# New_U540.net
KiCad netlist of a schematic drawn in EAGLE
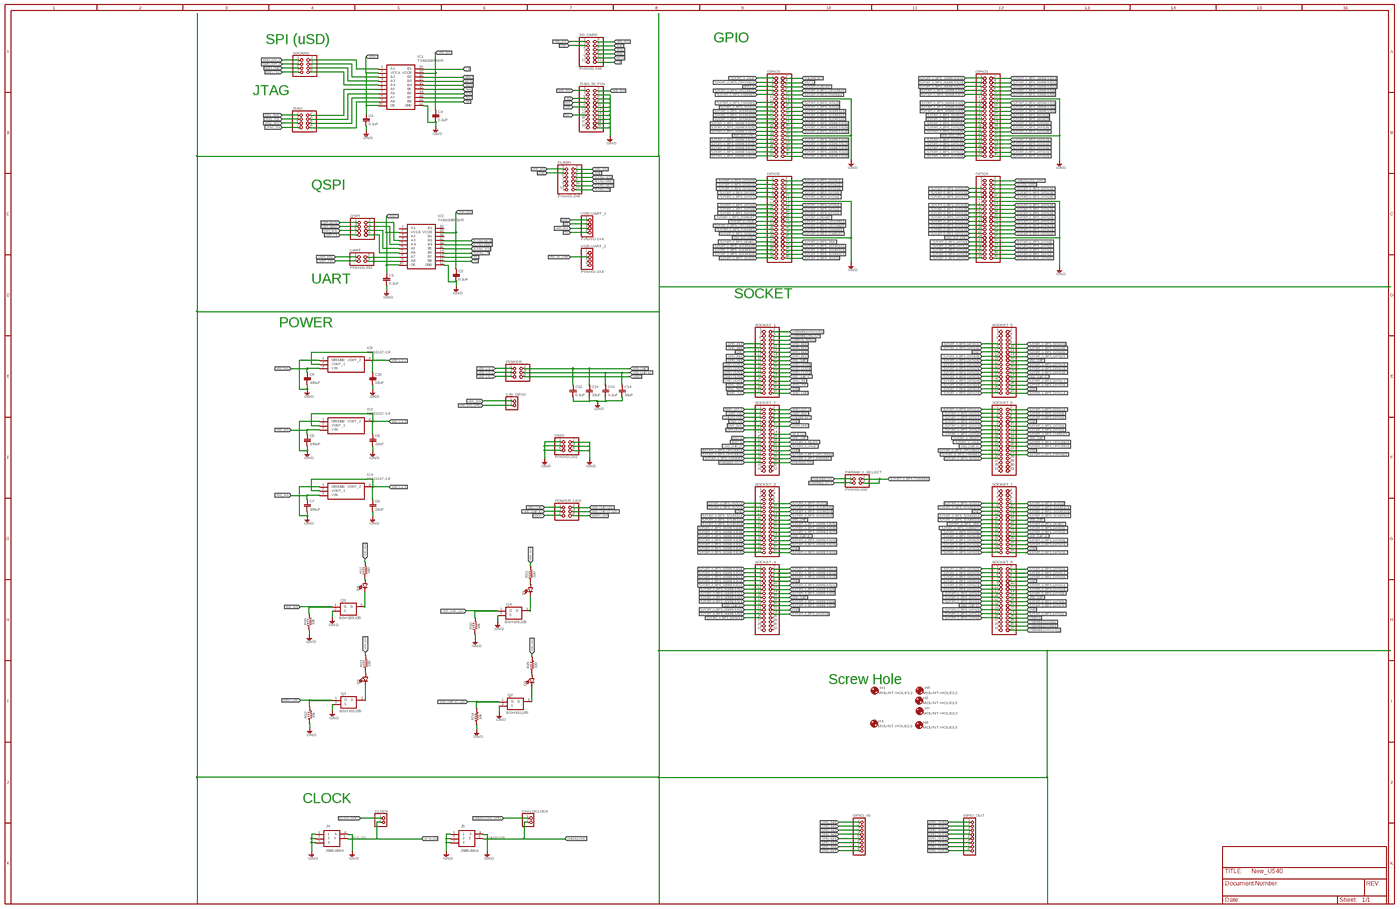
[diagram p0: schematic, sheet 1, overview]
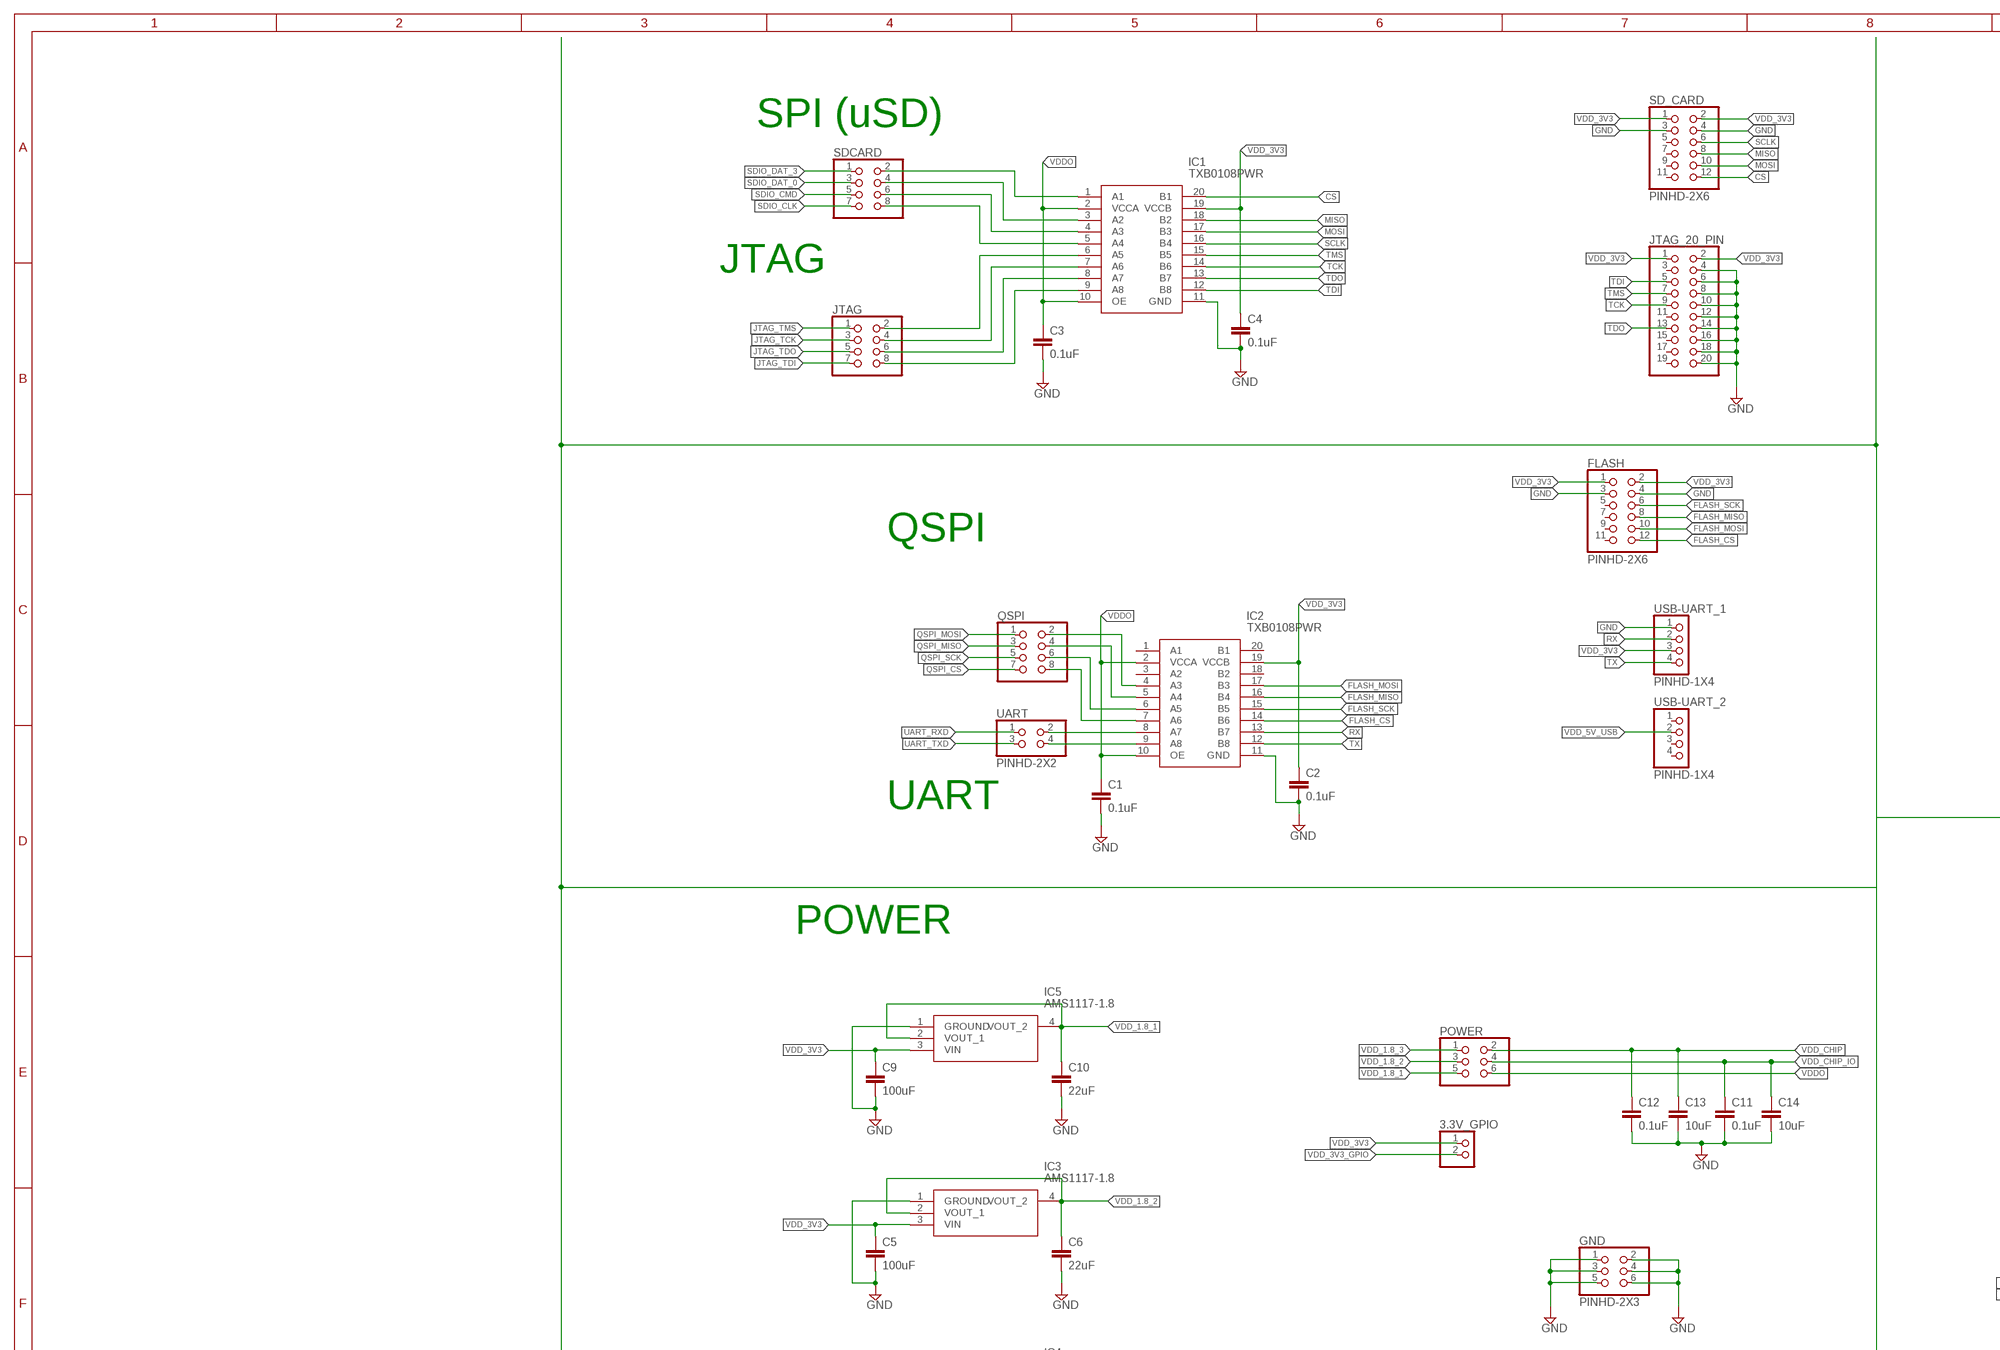
[diagram p1: schematic, sheet 1, part 1 of 4]
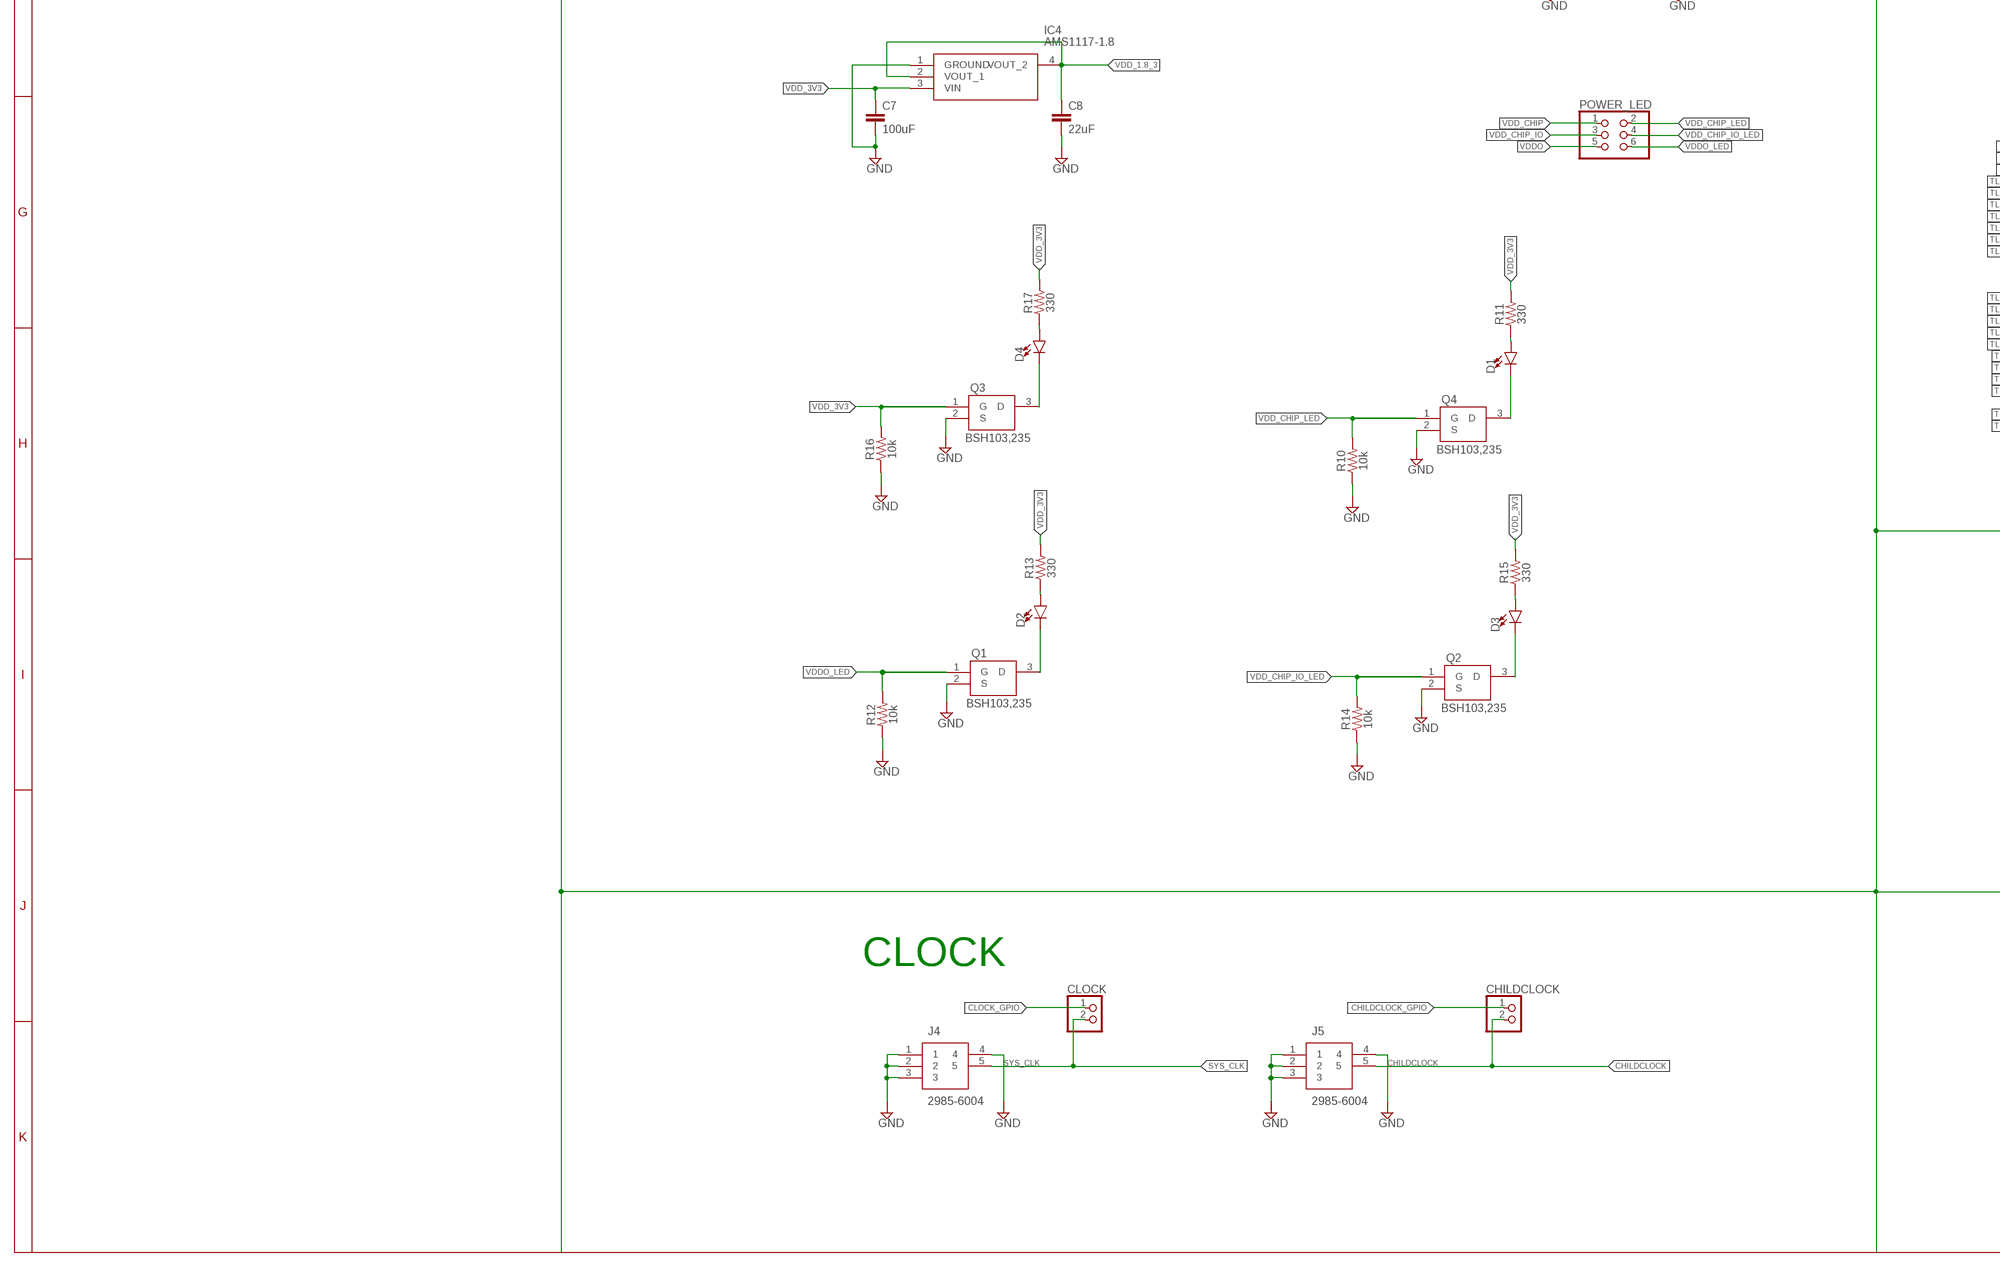
[diagram p2: schematic, sheet 1, part 2 of 4]
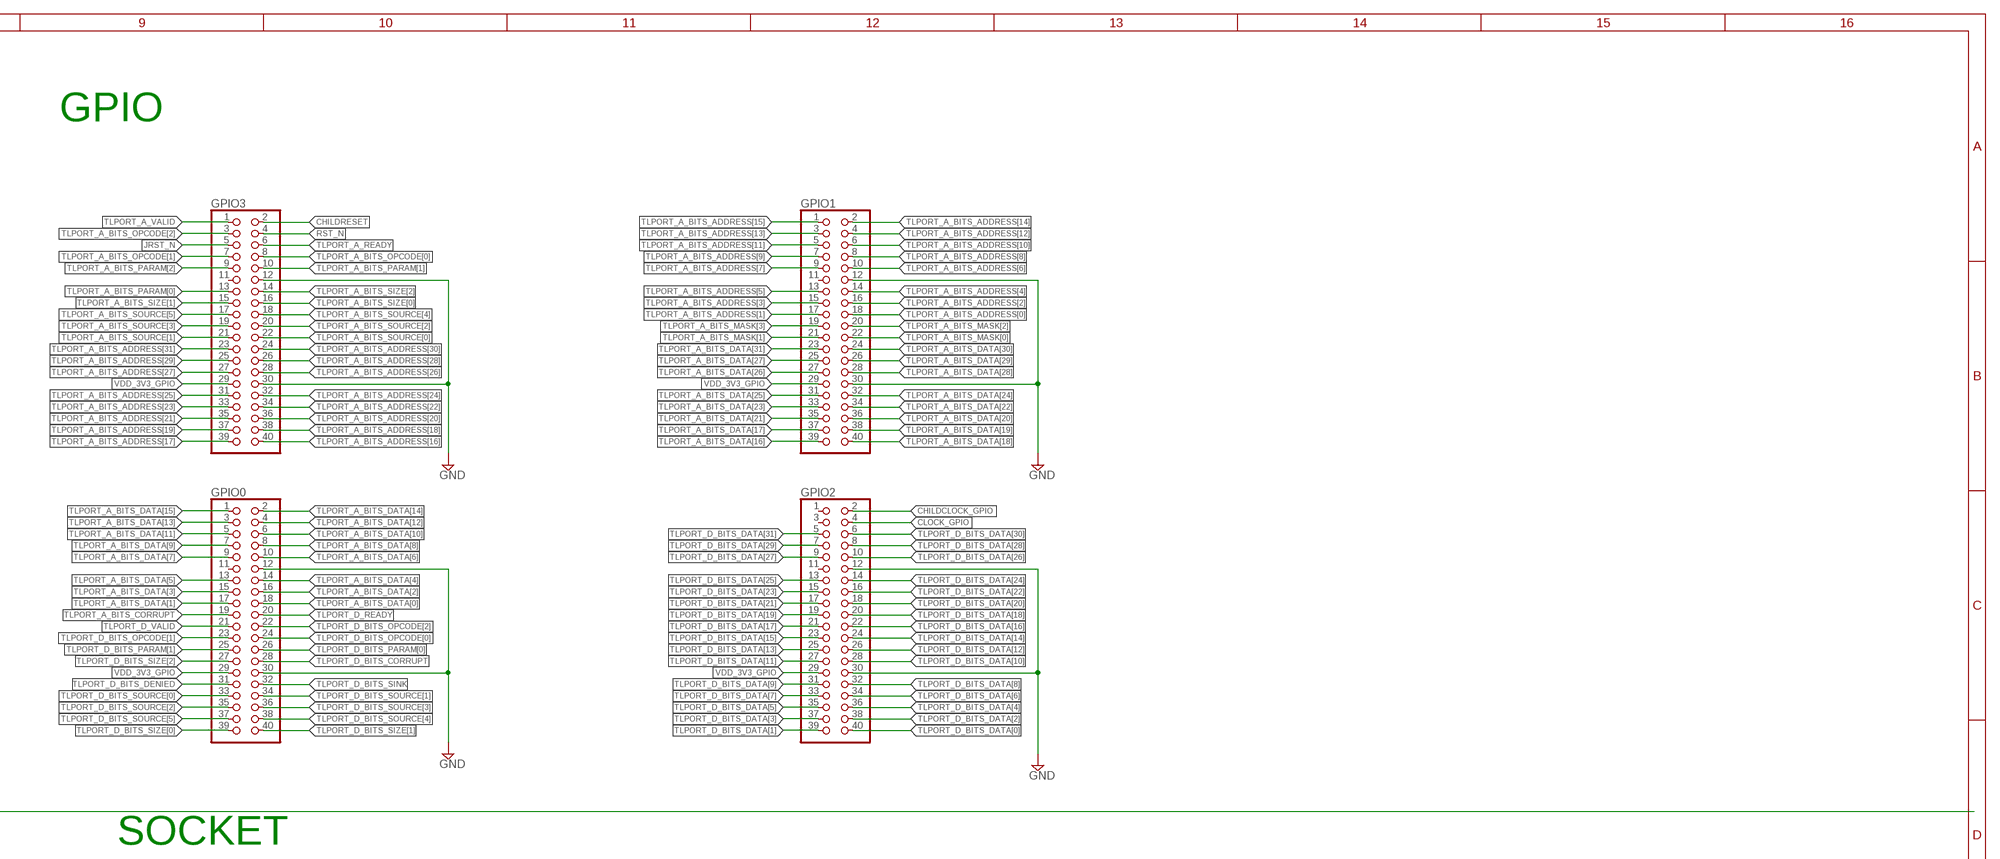
[diagram p3: schematic, sheet 1, part 3 of 4]
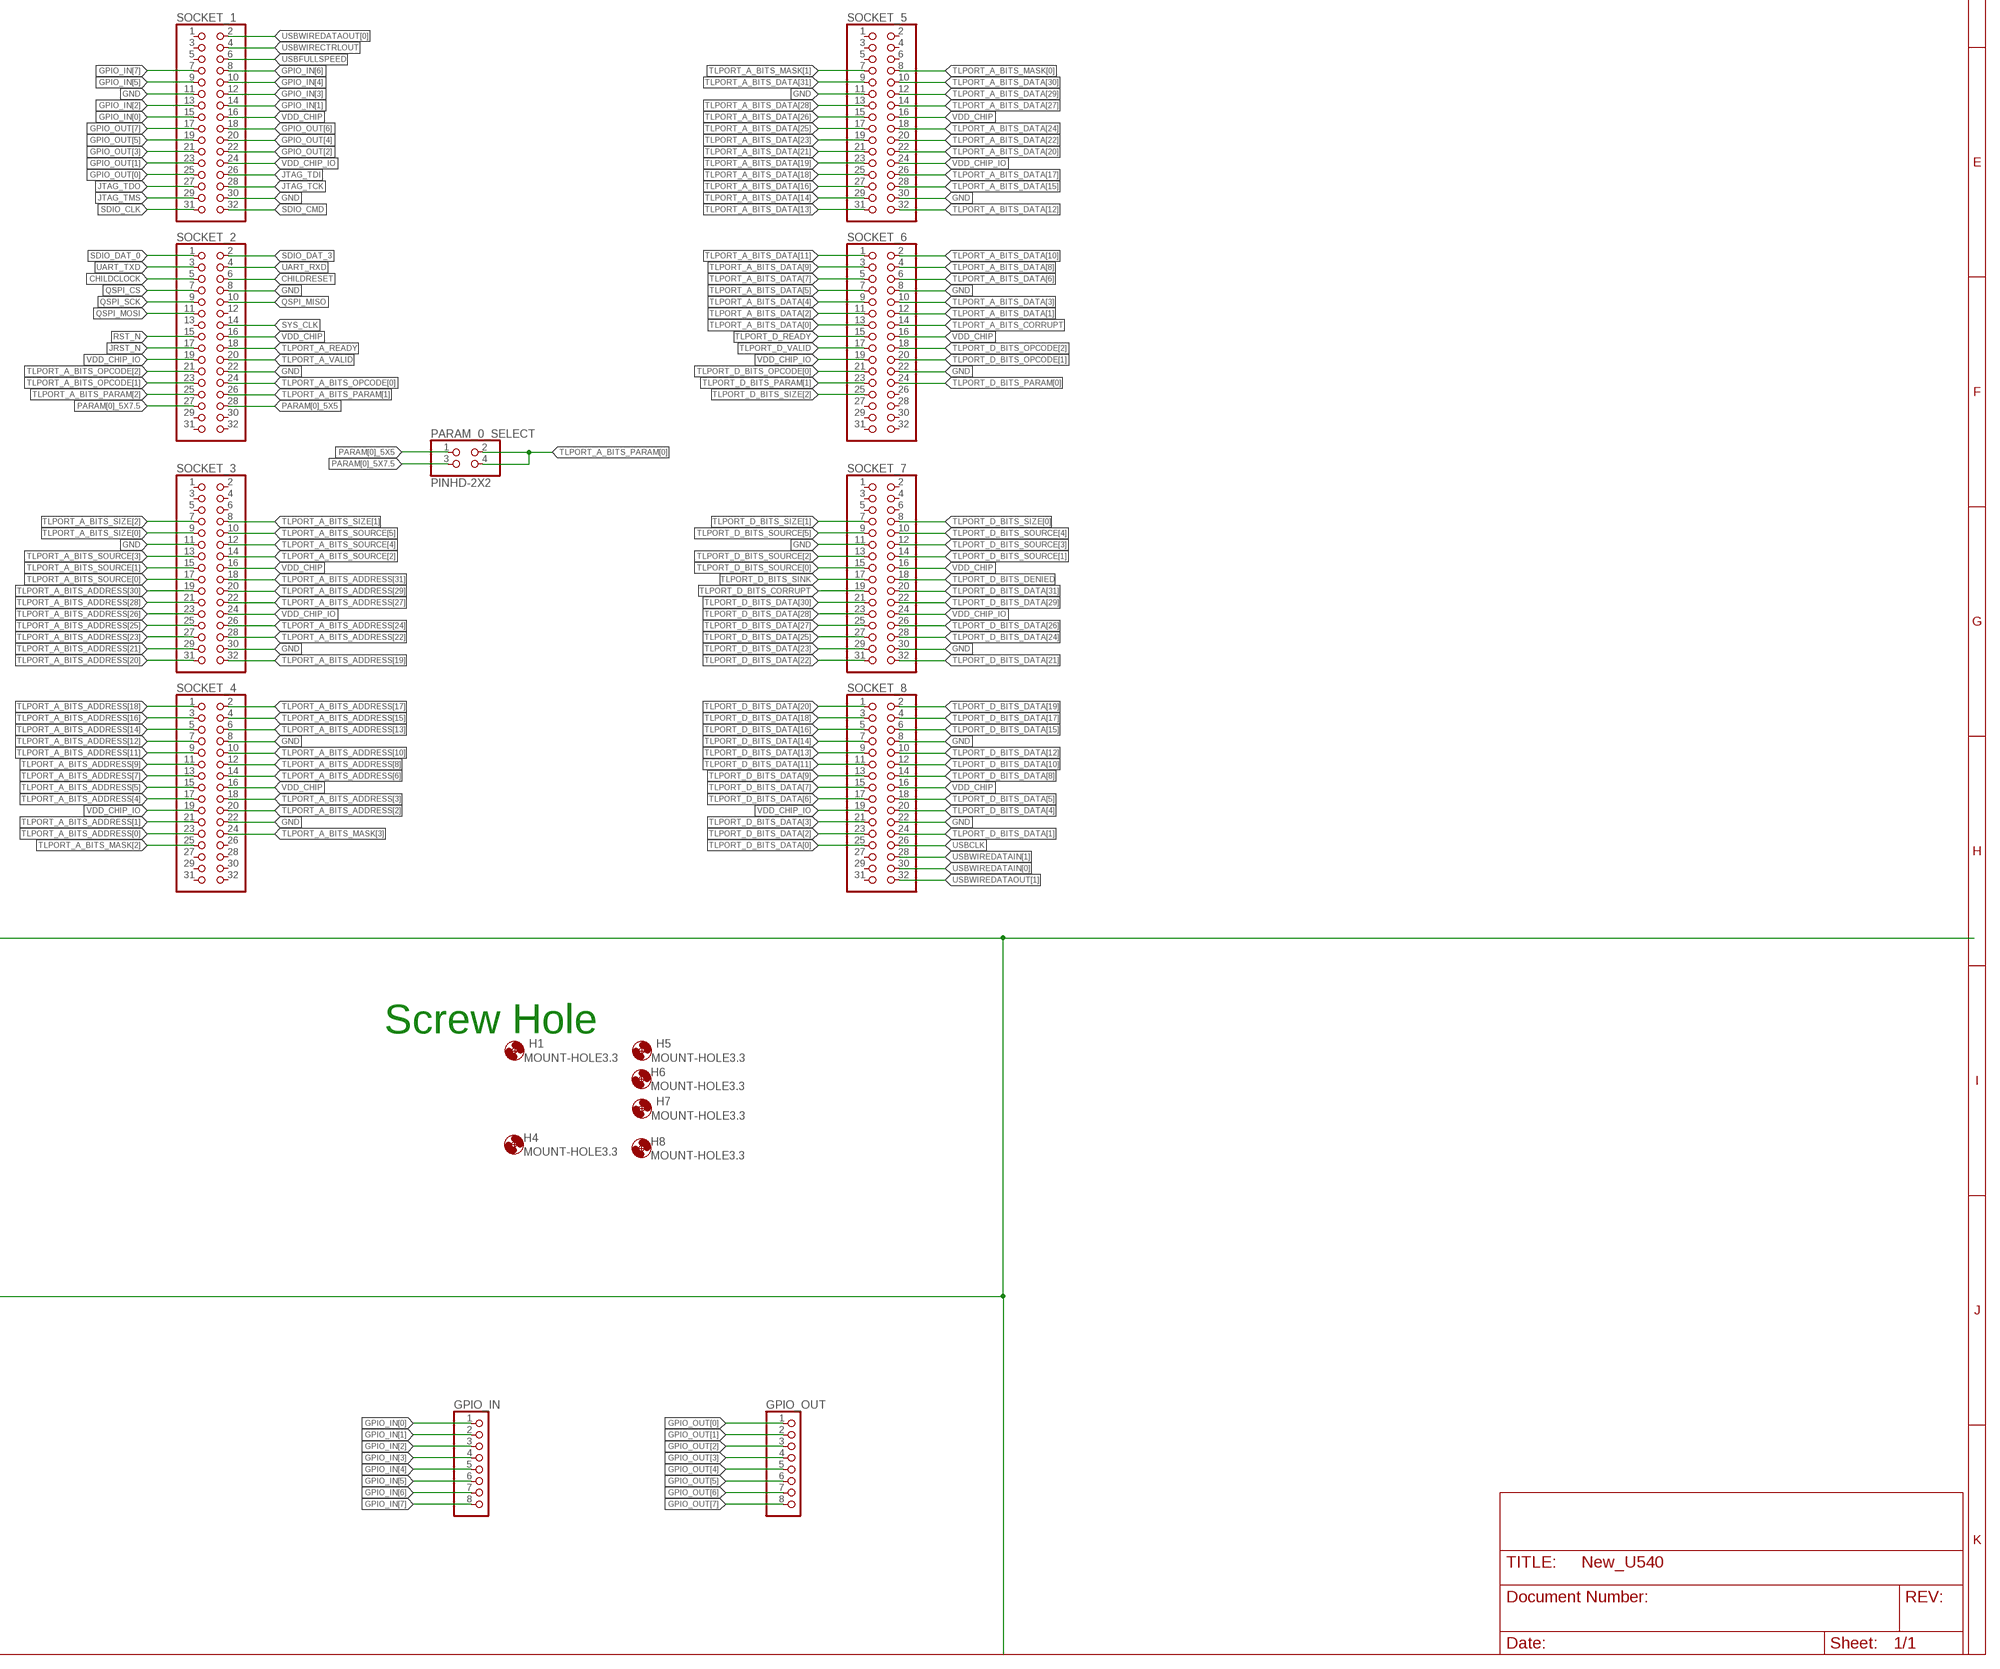
[diagram p4: schematic, sheet 1, part 4 of 4]

(export (version "E")
  (design (tool "Eeschema 10.0.6"))
  (components
    (comp (ref "3.3V_GPIO")
      (value "PINHD-1X2")
      (footprint "eagle-import:1X02")
      (libsource (lib "eagle-import") (part "PINHD-1X2"))
    )
    (comp (ref "C1")
      (value "0.1uF")
      (footprint "eagle-import:1206")
      (libsource (lib "eagle-import") (part "1.0UF-1206-50V-10%"))
    )
    (comp (ref "C2")
      (value "0.1uF")
      (footprint "eagle-import:1206")
      (libsource (lib "eagle-import") (part "1.0UF-1206-50V-10%"))
    )
    (comp (ref "C3")
      (value "0.1uF")
      (footprint "eagle-import:1206")
      (libsource (lib "eagle-import") (part "1.0UF-1206-50V-10%"))
    )
    (comp (ref "C4")
      (value "0.1uF")
      (footprint "eagle-import:1206")
      (libsource (lib "eagle-import") (part "1.0UF-1206-50V-10%"))
    )
    (comp (ref "C5")
      (value "100uF")
      (footprint "eagle-import:1206")
      (libsource (lib "eagle-import") (part "1.0UF-1206-50V-10%"))
    )
    (comp (ref "C6")
      (value "22uF")
      (footprint "eagle-import:1206")
      (libsource (lib "eagle-import") (part "1.0UF-1206-50V-10%"))
    )
    (comp (ref "C7")
      (value "100uF")
      (footprint "eagle-import:1206")
      (libsource (lib "eagle-import") (part "1.0UF-1206-50V-10%"))
    )
    (comp (ref "C8")
      (value "22uF")
      (footprint "eagle-import:1206")
      (libsource (lib "eagle-import") (part "1.0UF-1206-50V-10%"))
    )
    (comp (ref "C9")
      (value "100uF")
      (footprint "eagle-import:1206")
      (libsource (lib "eagle-import") (part "1.0UF-1206-50V-10%"))
    )
    (comp (ref "C10")
      (value "22uF")
      (footprint "eagle-import:1206")
      (libsource (lib "eagle-import") (part "1.0UF-1206-50V-10%"))
    )
    (comp (ref "C11")
      (value "0.1uF")
      (footprint "eagle-import:1206")
      (libsource (lib "eagle-import") (part "1.0UF-1206-50V-10%"))
    )
    (comp (ref "C12")
      (value "0.1uF")
      (footprint "eagle-import:1206")
      (libsource (lib "eagle-import") (part "1.0UF-1206-50V-10%"))
    )
    (comp (ref "C13")
      (value "10uF")
      (footprint "eagle-import:1206")
      (libsource (lib "eagle-import") (part "1.0UF-1206-50V-10%"))
    )
    (comp (ref "C14")
      (value "10uF")
      (footprint "eagle-import:1206")
      (libsource (lib "eagle-import") (part "1.0UF-1206-50V-10%"))
    )
    (comp (ref "CHILDCLOCK")
      (value "PINHD-1X2")
      (footprint "eagle-import:1X02")
      (libsource (lib "eagle-import") (part "PINHD-1X2"))
    )
    (comp (ref "CLOCK")
      (value "PINHD-1X2")
      (footprint "eagle-import:1X02")
      (libsource (lib "eagle-import") (part "PINHD-1X2"))
    )
    (comp (ref "D1")
      (value "LED1206")
      (footprint "eagle-import:LED-1206")
      (libsource (lib "eagle-import") (part "LED1206"))
    )
    (comp (ref "D2")
      (value "LED1206")
      (footprint "eagle-import:LED-1206")
      (libsource (lib "eagle-import") (part "LED1206"))
    )
    (comp (ref "D3")
      (value "LED1206")
      (footprint "eagle-import:LED-1206")
      (libsource (lib "eagle-import") (part "LED1206"))
    )
    (comp (ref "D4")
      (value "LED1206")
      (footprint "eagle-import:LED-1206")
      (libsource (lib "eagle-import") (part "LED1206"))
    )
    (comp (ref "FLASH")
      (value "PINHD-2X6")
      (footprint "eagle-import:2X06")
      (libsource (lib "eagle-import") (part "PINHD-2X6"))
    )
    (comp (ref "GND")
      (value "PINHD-2X3")
      (footprint "eagle-import:2X03")
      (libsource (lib "eagle-import") (part "PINHD-2X3"))
    )
    (comp (ref "GPIO0")
      (value "PINHD-2X20")
      (footprint "eagle-import:2X20")
      (libsource (lib "eagle-import") (part "PINHD-2X20"))
    )
    (comp (ref "GPIO1")
      (value "PINHD-2X20")
      (footprint "eagle-import:2X20")
      (libsource (lib "eagle-import") (part "PINHD-2X20"))
    )
    (comp (ref "GPIO2")
      (value "PINHD-2X20")
      (footprint "eagle-import:2X20")
      (libsource (lib "eagle-import") (part "PINHD-2X20"))
    )
    (comp (ref "GPIO3")
      (value "PINHD-2X20")
      (footprint "eagle-import:2X20")
      (libsource (lib "eagle-import") (part "PINHD-2X20"))
    )
    (comp (ref "GPIO_IN")
      (value "PINHD-1X8")
      (footprint "eagle-import:1X08")
      (libsource (lib "eagle-import") (part "PINHD-1X8"))
    )
    (comp (ref "GPIO_OUT")
      (value "PINHD-1X8")
      (footprint "eagle-import:1X08")
      (libsource (lib "eagle-import") (part "PINHD-1X8"))
    )
    (comp (ref "H1")
      (value "MOUNT-HOLE3.3")
      (footprint "eagle-import:3,3")
      (libsource (lib "eagle-import") (part "MOUNT-HOLE3.3"))
    )
    (comp (ref "H4")
      (value "MOUNT-HOLE3.3")
      (footprint "eagle-import:3,3")
      (libsource (lib "eagle-import") (part "MOUNT-HOLE3.3"))
    )
    (comp (ref "H5")
      (value "MOUNT-HOLE3.3")
      (footprint "eagle-import:3,3")
      (libsource (lib "eagle-import") (part "MOUNT-HOLE3.3"))
    )
    (comp (ref "H6")
      (value "MOUNT-HOLE3.3")
      (footprint "eagle-import:3,3")
      (libsource (lib "eagle-import") (part "MOUNT-HOLE3.3"))
    )
    (comp (ref "H7")
      (value "MOUNT-HOLE3.3")
      (footprint "eagle-import:3,3")
      (libsource (lib "eagle-import") (part "MOUNT-HOLE3.3"))
    )
    (comp (ref "H8")
      (value "MOUNT-HOLE3.3")
      (footprint "eagle-import:3,3")
      (libsource (lib "eagle-import") (part "MOUNT-HOLE3.3"))
    )
    (comp (ref "IC1")
      (value "TXB0108PWR")
      (footprint "eagle-import:SOP65P640X120-20N")
      (fields (field (name "MOUSER_PART_NUMBER") "595-TXB0108PWR"))
      (libsource (lib "eagle-import") (part "TXB0108PWR"))
    )
    (comp (ref "IC2")
      (value "TXB0108PWR")
      (footprint "eagle-import:SOP65P640X120-20N")
      (fields (field (name "MOUSER_PART_NUMBER") "595-TXB0108PWR"))
      (libsource (lib "eagle-import") (part "TXB0108PWR"))
    )
    (comp (ref "IC3")
      (value "AMS1117-1.8")
      (footprint "eagle-import:SOT229P700X180-4N")
      (fields (field (name "MANUFACTURER_PART_NUMBER") "AMS1117"))
      (libsource (lib "eagle-import") (part "AMS1117"))
    )
    (comp (ref "IC4")
      (value "AMS1117-1.8")
      (footprint "eagle-import:SOT229P700X180-4N")
      (fields (field (name "MANUFACTURER_PART_NUMBER") "AMS1117"))
      (libsource (lib "eagle-import") (part "AMS1117"))
    )
    (comp (ref "IC5")
      (value "AMS1117-1.8")
      (footprint "eagle-import:SOT229P700X180-4N")
      (fields (field (name "MANUFACTURER_PART_NUMBER") "AMS1117"))
      (libsource (lib "eagle-import") (part "AMS1117"))
    )
    (comp (ref "J4")
      (value "2985-6004")
      (footprint "eagle-import:29856004")
      (fields (field (name "MOUSER_PART_NUMBER") "523-2985-6004"))
      (libsource (lib "eagle-import") (part "2985-6004"))
    )
    (comp (ref "J5")
      (value "2985-6004")
      (footprint "eagle-import:29856004")
      (fields (field (name "MOUSER_PART_NUMBER") "523-2985-6004"))
      (libsource (lib "eagle-import") (part "2985-6004"))
    )
    (comp (ref "JTAG")
      (value "PINHD-2X4")
      (footprint "eagle-import:2X04")
      (libsource (lib "eagle-import") (part "PINHD-2X4"))
    )
    (comp (ref "JTAG_20_PIN")
      (value "PINHD-2X10")
      (footprint "eagle-import:2X10")
      (libsource (lib "eagle-import") (part "PINHD-2X10"))
    )
    (comp (ref "PARAM_0_SELECT")
      (value "PINHD-2X2")
      (footprint "eagle-import:2X02")
      (libsource (lib "eagle-import") (part "PINHD-2X2"))
    )
    (comp (ref "POWER")
      (value "PINHD-2X3")
      (footprint "eagle-import:2X03")
      (libsource (lib "eagle-import") (part "pinhead_325_PINHD-2X3"))
    )
    (comp (ref "POWER_LED")
      (value "PINHD-2X3")
      (footprint "eagle-import:2X03")
      (libsource (lib "eagle-import") (part "pinhead_325_PINHD-2X3"))
    )
    (comp (ref "Q1")
      (value "BSH103,235")
      (footprint "eagle-import:SOT95P230X110-3N")
      (fields (field (name "MOUSER_PART_NUMBER") "771-BSH103235"))
      (libsource (lib "eagle-import") (part "BSH103,235"))
    )
    (comp (ref "Q2")
      (value "BSH103,235")
      (footprint "eagle-import:SOT95P230X110-3N")
      (fields (field (name "MOUSER_PART_NUMBER") "771-BSH103235"))
      (libsource (lib "eagle-import") (part "BSH103,235"))
    )
    (comp (ref "Q3")
      (value "BSH103,235")
      (footprint "eagle-import:SOT95P230X110-3N")
      (fields (field (name "MOUSER_PART_NUMBER") "771-BSH103235"))
      (libsource (lib "eagle-import") (part "BSH103,235"))
    )
    (comp (ref "Q4")
      (value "BSH103,235")
      (footprint "eagle-import:SOT95P230X110-3N")
      (fields (field (name "MOUSER_PART_NUMBER") "771-BSH103235"))
      (libsource (lib "eagle-import") (part "BSH103,235"))
    )
    (comp (ref "QSPI")
      (value "PINHD-2X4")
      (footprint "eagle-import:2X04")
      (libsource (lib "eagle-import") (part "PINHD-2X4"))
    )
    (comp (ref "R10")
      (value "10k")
      (footprint "eagle-import:1206")
      (libsource (lib "eagle-import") (part "RESISTOR1206"))
    )
    (comp (ref "R11")
      (value "330")
      (footprint "eagle-import:1206")
      (libsource (lib "eagle-import") (part "RESISTOR1206"))
    )
    (comp (ref "R12")
      (value "10k")
      (footprint "eagle-import:1206")
      (libsource (lib "eagle-import") (part "RESISTOR1206"))
    )
    (comp (ref "R13")
      (value "330")
      (footprint "eagle-import:1206")
      (libsource (lib "eagle-import") (part "RESISTOR1206"))
    )
    (comp (ref "R14")
      (value "10k")
      (footprint "eagle-import:1206")
      (libsource (lib "eagle-import") (part "RESISTOR1206"))
    )
    (comp (ref "R15")
      (value "330")
      (footprint "eagle-import:1206")
      (libsource (lib "eagle-import") (part "RESISTOR1206"))
    )
    (comp (ref "R16")
      (value "10k")
      (footprint "eagle-import:1206")
      (libsource (lib "eagle-import") (part "RESISTOR1206"))
    )
    (comp (ref "R17")
      (value "330")
      (footprint "eagle-import:1206")
      (libsource (lib "eagle-import") (part "RESISTOR1206"))
    )
    (comp (ref "SDCARD")
      (value "PINHD-2X4")
      (footprint "eagle-import:2X04")
      (libsource (lib "eagle-import") (part "PINHD-2X4"))
    )
    (comp (ref "SD_CARD")
      (value "PINHD-2X6")
      (footprint "eagle-import:2X06")
      (libsource (lib "eagle-import") (part "PINHD-2X6"))
    )
    (comp (ref "SOCKET_1")
      (value "PINHD-2X16")
      (footprint "eagle-import:2X16")
      (libsource (lib "eagle-import") (part "PINHD-2X16"))
    )
    (comp (ref "SOCKET_2")
      (value "PINHD-2X16")
      (footprint "eagle-import:2X16")
      (libsource (lib "eagle-import") (part "PINHD-2X16"))
    )
    (comp (ref "SOCKET_3")
      (value "PINHD-2X16")
      (footprint "eagle-import:2X16")
      (libsource (lib "eagle-import") (part "PINHD-2X16"))
    )
    (comp (ref "SOCKET_4")
      (value "PINHD-2X16")
      (footprint "eagle-import:2X16")
      (libsource (lib "eagle-import") (part "PINHD-2X16"))
    )
    (comp (ref "SOCKET_5")
      (value "PINHD-2X16")
      (footprint "eagle-import:2X16")
      (libsource (lib "eagle-import") (part "PINHD-2X16"))
    )
    (comp (ref "SOCKET_6")
      (value "PINHD-2X16")
      (footprint "eagle-import:2X16")
      (libsource (lib "eagle-import") (part "PINHD-2X16"))
    )
    (comp (ref "SOCKET_7")
      (value "PINHD-2X16")
      (footprint "eagle-import:2X16")
      (libsource (lib "eagle-import") (part "PINHD-2X16"))
    )
    (comp (ref "SOCKET_8")
      (value "PINHD-2X16")
      (footprint "eagle-import:2X16")
      (libsource (lib "eagle-import") (part "PINHD-2X16"))
    )
    (comp (ref "UART")
      (value "PINHD-2X2")
      (footprint "eagle-import:2X02")
      (libsource (lib "eagle-import") (part "PINHD-2X2"))
    )
    (comp (ref "USB-UART_1")
      (value "PINHD-1X4")
      (footprint "eagle-import:1X04")
      (libsource (lib "eagle-import") (part "PINHD-1X4"))
    )
    (comp (ref "USB-UART_2")
      (value "PINHD-1X4")
      (footprint "eagle-import:1X04")
      (libsource (lib "eagle-import") (part "PINHD-1X4"))
    )
  )
  (nets
    (net (code "1") (name "CHILDCLOCK") (class "Default")
      (node (ref "CHILDCLOCK") (pin "2") (pinfunction "2_2") (pintype "passive"))
      (node (ref "J5") (pin "5") (pinfunction "5_5") (pintype "bidirectional"))
      (node (ref "SOCKET_2") (pin "5") (pinfunction "5_5") (pintype "passive"))
    )
    (net (code "2") (name "CHILDCLOCK_GPIO") (class "Default")
      (node (ref "CHILDCLOCK") (pin "1") (pinfunction "1_1") (pintype "passive"))
      (node (ref "GPIO2") (pin "2") (pinfunction "2_2") (pintype "passive"))
    )
    (net (code "3") (name "CHILDRESET") (class "Default")
      (node (ref "GPIO3") (pin "2") (pinfunction "2_2") (pintype "passive"))
      (node (ref "SOCKET_2") (pin "6") (pinfunction "6_6") (pintype "passive"))
    )
    (net (code "4") (name "CLOCK_GPIO") (class "Default")
      (node (ref "CLOCK") (pin "1") (pinfunction "1_1") (pintype "passive"))
      (node (ref "GPIO2") (pin "4") (pinfunction "4_4") (pintype "passive"))
    )
    (net (code "5") (name "CS") (class "Default")
      (node (ref "IC1") (pin "20") (pinfunction "B1_20") (pintype "bidirectional"))
      (node (ref "SD_CARD") (pin "12") (pinfunction "12_12") (pintype "passive"))
    )
    (net (code "6") (name "FLASH_CS") (class "Default")
      (node (ref "FLASH") (pin "12") (pinfunction "12_12") (pintype "passive"))
      (node (ref "IC2") (pin "14") (pinfunction "B6_14") (pintype "bidirectional"))
    )
    (net (code "7") (name "FLASH_MISO") (class "Default")
      (node (ref "FLASH") (pin "8") (pinfunction "8_8") (pintype "passive"))
      (node (ref "IC2") (pin "16") (pinfunction "B4_16") (pintype "bidirectional"))
    )
    (net (code "8") (name "FLASH_MOSI") (class "Default")
      (node (ref "FLASH") (pin "10") (pinfunction "10_10") (pintype "passive"))
      (node (ref "IC2") (pin "17") (pinfunction "B3_17") (pintype "bidirectional"))
    )
    (net (code "9") (name "FLASH_SCK") (class "Default")
      (node (ref "FLASH") (pin "6") (pinfunction "6_6") (pintype "passive"))
      (node (ref "IC2") (pin "15") (pinfunction "B5_15") (pintype "bidirectional"))
    )
    (net (code "10") (name "GND") (class "Default")
      (node (ref "C1") (pin "2") (pinfunction "2_2") (pintype "passive"))
      (node (ref "C10") (pin "2") (pinfunction "2_2") (pintype "passive"))
      (node (ref "C11") (pin "2") (pinfunction "2_2") (pintype "passive"))
      (node (ref "C12") (pin "2") (pinfunction "2_2") (pintype "passive"))
      (node (ref "C13") (pin "2") (pinfunction "2_2") (pintype "passive"))
      (node (ref "C14") (pin "2") (pinfunction "2_2") (pintype "passive"))
      (node (ref "C2") (pin "2") (pinfunction "2_2") (pintype "passive"))
      (node (ref "C3") (pin "2") (pinfunction "2_2") (pintype "passive"))
      (node (ref "C4") (pin "2") (pinfunction "2_2") (pintype "passive"))
      (node (ref "C5") (pin "2") (pinfunction "2_2") (pintype "passive"))
      (node (ref "C6") (pin "2") (pinfunction "2_2") (pintype "passive"))
      (node (ref "C7") (pin "2") (pinfunction "2_2") (pintype "passive"))
      (node (ref "C8") (pin "2") (pinfunction "2_2") (pintype "passive"))
      (node (ref "C9") (pin "2") (pinfunction "2_2") (pintype "passive"))
      (node (ref "FLASH") (pin "3") (pinfunction "3_3") (pintype "passive"))
      (node (ref "FLASH") (pin "4") (pinfunction "4_4") (pintype "passive"))
      (node (ref "GND") (pin "1") (pinfunction "1_1") (pintype "passive"))
      (node (ref "GND") (pin "2") (pinfunction "2_2") (pintype "passive"))
      (node (ref "GND") (pin "3") (pinfunction "3_3") (pintype "passive"))
      (node (ref "GND") (pin "4") (pinfunction "4_4") (pintype "passive"))
      (node (ref "GND") (pin "5") (pinfunction "5_5") (pintype "passive"))
      (node (ref "GND") (pin "6") (pinfunction "6_6") (pintype "passive"))
      (node (ref "GPIO0") (pin "12") (pinfunction "12_12") (pintype "passive"))
      (node (ref "GPIO0") (pin "30") (pinfunction "30_30") (pintype "passive"))
      (node (ref "GPIO1") (pin "12") (pinfunction "12_12") (pintype "passive"))
      (node (ref "GPIO1") (pin "30") (pinfunction "30_30") (pintype "passive"))
      (node (ref "GPIO2") (pin "12") (pinfunction "12_12") (pintype "passive"))
      (node (ref "GPIO2") (pin "30") (pinfunction "30_30") (pintype "passive"))
      (node (ref "GPIO3") (pin "12") (pinfunction "12_12") (pintype "passive"))
      (node (ref "GPIO3") (pin "30") (pinfunction "30_30") (pintype "passive"))
      (node (ref "IC1") (pin "11") (pinfunction "GND_11") (pintype "bidirectional"))
      (node (ref "IC2") (pin "11") (pinfunction "GND_11") (pintype "bidirectional"))
      (node (ref "IC3") (pin "1") (pinfunction "GROUND_1") (pintype "bidirectional"))
      (node (ref "IC4") (pin "1") (pinfunction "GROUND_1") (pintype "bidirectional"))
      (node (ref "IC5") (pin "1") (pinfunction "GROUND_1") (pintype "bidirectional"))
      (node (ref "J4") (pin "1") (pinfunction "1_1") (pintype "bidirectional"))
      (node (ref "J4") (pin "2") (pinfunction "2_2") (pintype "bidirectional"))
      (node (ref "J4") (pin "3") (pinfunction "3_3") (pintype "bidirectional"))
      (node (ref "J4") (pin "4") (pinfunction "4_4") (pintype "bidirectional"))
      (node (ref "J5") (pin "1") (pinfunction "1_1") (pintype "bidirectional"))
      (node (ref "J5") (pin "2") (pinfunction "2_2") (pintype "bidirectional"))
      (node (ref "J5") (pin "3") (pinfunction "3_3") (pintype "bidirectional"))
      (node (ref "J5") (pin "4") (pinfunction "4_4") (pintype "bidirectional"))
      (node (ref "JTAG_20_PIN") (pin "10") (pinfunction "10_10") (pintype "passive"))
      (node (ref "JTAG_20_PIN") (pin "12") (pinfunction "12_12") (pintype "passive"))
      (node (ref "JTAG_20_PIN") (pin "14") (pinfunction "14_14") (pintype "passive"))
      (node (ref "JTAG_20_PIN") (pin "16") (pinfunction "16_16") (pintype "passive"))
      (node (ref "JTAG_20_PIN") (pin "18") (pinfunction "18_18") (pintype "passive"))
      (node (ref "JTAG_20_PIN") (pin "20") (pinfunction "20_20") (pintype "passive"))
      (node (ref "JTAG_20_PIN") (pin "4") (pinfunction "4_4") (pintype "passive"))
      (node (ref "JTAG_20_PIN") (pin "6") (pinfunction "6_6") (pintype "passive"))
      (node (ref "JTAG_20_PIN") (pin "8") (pinfunction "8_8") (pintype "passive"))
      (node (ref "Q1") (pin "2") (pinfunction "S_2") (pintype "bidirectional"))
      (node (ref "Q2") (pin "2") (pinfunction "S_2") (pintype "bidirectional"))
      (node (ref "Q3") (pin "2") (pinfunction "S_2") (pintype "bidirectional"))
      (node (ref "Q4") (pin "2") (pinfunction "S_2") (pintype "bidirectional"))
      (node (ref "R10") (pin "1") (pinfunction "1_1") (pintype "passive"))
      (node (ref "R12") (pin "1") (pinfunction "1_1") (pintype "passive"))
      (node (ref "R14") (pin "1") (pinfunction "1_1") (pintype "passive"))
      (node (ref "R16") (pin "1") (pinfunction "1_1") (pintype "passive"))
      (node (ref "SD_CARD") (pin "3") (pinfunction "3_3") (pintype "passive"))
      (node (ref "SD_CARD") (pin "4") (pinfunction "4_4") (pintype "passive"))
      (node (ref "SOCKET_1") (pin "11") (pinfunction "11_11") (pintype "passive"))
      (node (ref "SOCKET_1") (pin "30") (pinfunction "30_30") (pintype "passive"))
      (node (ref "SOCKET_2") (pin "22") (pinfunction "22_22") (pintype "passive"))
      (node (ref "SOCKET_2") (pin "8") (pinfunction "8_8") (pintype "passive"))
      (node (ref "SOCKET_3") (pin "11") (pinfunction "11_11") (pintype "passive"))
      (node (ref "SOCKET_3") (pin "30") (pinfunction "30_30") (pintype "passive"))
      (node (ref "SOCKET_4") (pin "22") (pinfunction "22_22") (pintype "passive"))
      (node (ref "SOCKET_4") (pin "8") (pinfunction "8_8") (pintype "passive"))
      (node (ref "SOCKET_5") (pin "11") (pinfunction "11_11") (pintype "passive"))
      (node (ref "SOCKET_5") (pin "30") (pinfunction "30_30") (pintype "passive"))
      (node (ref "SOCKET_6") (pin "22") (pinfunction "22_22") (pintype "passive"))
      (node (ref "SOCKET_6") (pin "8") (pinfunction "8_8") (pintype "passive"))
      (node (ref "SOCKET_7") (pin "11") (pinfunction "11_11") (pintype "passive"))
      (node (ref "SOCKET_7") (pin "30") (pinfunction "30_30") (pintype "passive"))
      (node (ref "SOCKET_8") (pin "22") (pinfunction "22_22") (pintype "passive"))
      (node (ref "SOCKET_8") (pin "8") (pinfunction "8_8") (pintype "passive"))
      (node (ref "USB-UART_1") (pin "1") (pinfunction "1_1") (pintype "passive"))
    )
    (net (code "11") (name "GPIO_IN[0]") (class "Default")
      (node (ref "GPIO_IN") (pin "1") (pinfunction "1_1") (pintype "passive"))
      (node (ref "SOCKET_1") (pin "15") (pinfunction "15_15") (pintype "passive"))
    )
    (net (code "12") (name "GPIO_IN[1]") (class "Default")
      (node (ref "GPIO_IN") (pin "2") (pinfunction "2_2") (pintype "passive"))
      (node (ref "SOCKET_1") (pin "14") (pinfunction "14_14") (pintype "passive"))
    )
    (net (code "13") (name "GPIO_IN[2]") (class "Default")
      (node (ref "GPIO_IN") (pin "3") (pinfunction "3_3") (pintype "passive"))
      (node (ref "SOCKET_1") (pin "13") (pinfunction "13_13") (pintype "passive"))
    )
    (net (code "14") (name "GPIO_IN[3]") (class "Default")
      (node (ref "GPIO_IN") (pin "4") (pinfunction "4_4") (pintype "passive"))
      (node (ref "SOCKET_1") (pin "12") (pinfunction "12_12") (pintype "passive"))
    )
    (net (code "15") (name "GPIO_IN[4]") (class "Default")
      (node (ref "GPIO_IN") (pin "5") (pinfunction "5_5") (pintype "passive"))
      (node (ref "SOCKET_1") (pin "10") (pinfunction "10_10") (pintype "passive"))
    )
    (net (code "16") (name "GPIO_IN[5]") (class "Default")
      (node (ref "GPIO_IN") (pin "6") (pinfunction "6_6") (pintype "passive"))
      (node (ref "SOCKET_1") (pin "9") (pinfunction "9_9") (pintype "passive"))
    )
    (net (code "17") (name "GPIO_IN[6]") (class "Default")
      (node (ref "GPIO_IN") (pin "7") (pinfunction "7_7") (pintype "passive"))
      (node (ref "SOCKET_1") (pin "8") (pinfunction "8_8") (pintype "passive"))
    )
    (net (code "18") (name "GPIO_IN[7]") (class "Default")
      (node (ref "GPIO_IN") (pin "8") (pinfunction "8_8") (pintype "passive"))
      (node (ref "SOCKET_1") (pin "7") (pinfunction "7_7") (pintype "passive"))
    )
    (net (code "19") (name "GPIO_OUT[0]") (class "Default")
      (node (ref "GPIO_OUT") (pin "1") (pinfunction "1_1") (pintype "passive"))
      (node (ref "SOCKET_1") (pin "25") (pinfunction "25_25") (pintype "passive"))
    )
    (net (code "20") (name "GPIO_OUT[1]") (class "Default")
      (node (ref "GPIO_OUT") (pin "2") (pinfunction "2_2") (pintype "passive"))
      (node (ref "SOCKET_1") (pin "23") (pinfunction "23_23") (pintype "passive"))
    )
    (net (code "21") (name "GPIO_OUT[2]") (class "Default")
      (node (ref "GPIO_OUT") (pin "3") (pinfunction "3_3") (pintype "passive"))
      (node (ref "SOCKET_1") (pin "22") (pinfunction "22_22") (pintype "passive"))
    )
    (net (code "22") (name "GPIO_OUT[3]") (class "Default")
      (node (ref "GPIO_OUT") (pin "4") (pinfunction "4_4") (pintype "passive"))
      (node (ref "SOCKET_1") (pin "21") (pinfunction "21_21") (pintype "passive"))
    )
    (net (code "23") (name "GPIO_OUT[4]") (class "Default")
      (node (ref "GPIO_OUT") (pin "5") (pinfunction "5_5") (pintype "passive"))
      (node (ref "SOCKET_1") (pin "20") (pinfunction "20_20") (pintype "passive"))
    )
    (net (code "24") (name "GPIO_OUT[5]") (class "Default")
      (node (ref "GPIO_OUT") (pin "6") (pinfunction "6_6") (pintype "passive"))
      (node (ref "SOCKET_1") (pin "19") (pinfunction "19_19") (pintype "passive"))
    )
    (net (code "25") (name "GPIO_OUT[6]") (class "Default")
      (node (ref "GPIO_OUT") (pin "7") (pinfunction "7_7") (pintype "passive"))
      (node (ref "SOCKET_1") (pin "18") (pinfunction "18_18") (pintype "passive"))
    )
    (net (code "26") (name "GPIO_OUT[7]") (class "Default")
      (node (ref "GPIO_OUT") (pin "8") (pinfunction "8_8") (pintype "passive"))
      (node (ref "SOCKET_1") (pin "17") (pinfunction "17_17") (pintype "passive"))
    )
    (net (code "27") (name "JRST_N") (class "Default")
      (node (ref "GPIO3") (pin "5") (pinfunction "5_5") (pintype "passive"))
      (node (ref "SOCKET_2") (pin "17") (pinfunction "17_17") (pintype "passive"))
    )
    (net (code "28") (name "JTAG_TCK") (class "Default")
      (node (ref "JTAG") (pin "3") (pinfunction "3_3") (pintype "passive"))
      (node (ref "SOCKET_1") (pin "28") (pinfunction "28_28") (pintype "passive"))
    )
    (net (code "29") (name "JTAG_TDI") (class "Default")
      (node (ref "JTAG") (pin "7") (pinfunction "7_7") (pintype "passive"))
      (node (ref "SOCKET_1") (pin "26") (pinfunction "26_26") (pintype "passive"))
    )
    (net (code "30") (name "JTAG_TDO") (class "Default")
      (node (ref "JTAG") (pin "5") (pinfunction "5_5") (pintype "passive"))
      (node (ref "SOCKET_1") (pin "27") (pinfunction "27_27") (pintype "passive"))
    )
    (net (code "31") (name "JTAG_TMS") (class "Default")
      (node (ref "JTAG") (pin "1") (pinfunction "1_1") (pintype "passive"))
      (node (ref "SOCKET_1") (pin "29") (pinfunction "29_29") (pintype "passive"))
    )
    (net (code "32") (name "MISO") (class "Default")
      (node (ref "IC1") (pin "18") (pinfunction "B2_18") (pintype "bidirectional"))
      (node (ref "SD_CARD") (pin "8") (pinfunction "8_8") (pintype "passive"))
    )
    (net (code "33") (name "MOSI") (class "Default")
      (node (ref "IC1") (pin "17") (pinfunction "B3_17") (pintype "bidirectional"))
      (node (ref "SD_CARD") (pin "10") (pinfunction "10_10") (pintype "passive"))
    )
    (net (code "34") (name "Net-(D1-PadA)") (class "Default")
      (node (ref "D1") (pin "A") (pinfunction "A_A") (pintype "passive"))
      (node (ref "R11") (pin "1") (pinfunction "1_1") (pintype "passive"))
    )
    (net (code "35") (name "Net-(D2-PadA)") (class "Default")
      (node (ref "D2") (pin "A") (pinfunction "A_A") (pintype "passive"))
      (node (ref "R13") (pin "1") (pinfunction "1_1") (pintype "passive"))
    )
    (net (code "36") (name "Net-(D3-PadA)") (class "Default")
      (node (ref "D3") (pin "A") (pinfunction "A_A") (pintype "passive"))
      (node (ref "R15") (pin "1") (pinfunction "1_1") (pintype "passive"))
    )
    (net (code "37") (name "Net-(D4-PadA)") (class "Default")
      (node (ref "D4") (pin "A") (pinfunction "A_A") (pintype "passive"))
      (node (ref "R17") (pin "1") (pinfunction "1_1") (pintype "passive"))
    )
    (net (code "38") (name "Net-(IC1-A1)") (class "Default")
      (node (ref "IC1") (pin "1") (pinfunction "A1_1") (pintype "bidirectional"))
      (node (ref "SDCARD") (pin "2") (pinfunction "2_2") (pintype "passive"))
    )
    (net (code "39") (name "Net-(IC1-A2)") (class "Default")
      (node (ref "IC1") (pin "3") (pinfunction "A2_3") (pintype "bidirectional"))
      (node (ref "SDCARD") (pin "4") (pinfunction "4_4") (pintype "passive"))
    )
    (net (code "40") (name "Net-(IC1-A3)") (class "Default")
      (node (ref "IC1") (pin "4") (pinfunction "A3_4") (pintype "bidirectional"))
      (node (ref "SDCARD") (pin "6") (pinfunction "6_6") (pintype "passive"))
    )
    (net (code "41") (name "Net-(IC1-A4)") (class "Default")
      (node (ref "IC1") (pin "5") (pinfunction "A4_5") (pintype "bidirectional"))
      (node (ref "SDCARD") (pin "8") (pinfunction "8_8") (pintype "passive"))
    )
    (net (code "42") (name "Net-(IC1-A5)") (class "Default")
      (node (ref "IC1") (pin "6") (pinfunction "A5_6") (pintype "bidirectional"))
      (node (ref "JTAG") (pin "2") (pinfunction "2_2") (pintype "passive"))
    )
    (net (code "43") (name "Net-(IC1-A6)") (class "Default")
      (node (ref "IC1") (pin "7") (pinfunction "A6_7") (pintype "bidirectional"))
      (node (ref "JTAG") (pin "4") (pinfunction "4_4") (pintype "passive"))
    )
    (net (code "44") (name "Net-(IC1-A7)") (class "Default")
      (node (ref "IC1") (pin "8") (pinfunction "A7_8") (pintype "bidirectional"))
      (node (ref "JTAG") (pin "6") (pinfunction "6_6") (pintype "passive"))
    )
    (net (code "45") (name "Net-(IC1-A8)") (class "Default")
      (node (ref "IC1") (pin "9") (pinfunction "A8_9") (pintype "bidirectional"))
      (node (ref "JTAG") (pin "8") (pinfunction "8_8") (pintype "passive"))
    )
    (net (code "46") (name "Net-(IC2-A3)") (class "Default")
      (node (ref "IC2") (pin "4") (pinfunction "A3_4") (pintype "bidirectional"))
      (node (ref "QSPI") (pin "2") (pinfunction "2_2") (pintype "passive"))
    )
    (net (code "47") (name "Net-(IC2-A4)") (class "Default")
      (node (ref "IC2") (pin "5") (pinfunction "A4_5") (pintype "bidirectional"))
      (node (ref "QSPI") (pin "4") (pinfunction "4_4") (pintype "passive"))
    )
    (net (code "48") (name "Net-(IC2-A5)") (class "Default")
      (node (ref "IC2") (pin "6") (pinfunction "A5_6") (pintype "bidirectional"))
      (node (ref "QSPI") (pin "6") (pinfunction "6_6") (pintype "passive"))
    )
    (net (code "49") (name "Net-(IC2-A6)") (class "Default")
      (node (ref "IC2") (pin "7") (pinfunction "A6_7") (pintype "bidirectional"))
      (node (ref "QSPI") (pin "8") (pinfunction "8_8") (pintype "passive"))
    )
    (net (code "50") (name "Net-(IC2-A7)") (class "Default")
      (node (ref "IC2") (pin "8") (pinfunction "A7_8") (pintype "bidirectional"))
      (node (ref "UART") (pin "2") (pinfunction "2_2") (pintype "passive"))
    )
    (net (code "51") (name "Net-(IC2-A8)") (class "Default")
      (node (ref "IC2") (pin "9") (pinfunction "A8_9") (pintype "bidirectional"))
      (node (ref "UART") (pin "4") (pinfunction "4_4") (pintype "passive"))
    )
    (net (code "52") (name "Net-(Q1-D)") (class "Default")
      (node (ref "D2") (pin "C") (pinfunction "C_C") (pintype "passive"))
      (node (ref "Q1") (pin "3") (pinfunction "D_3") (pintype "bidirectional"))
    )
    (net (code "53") (name "Net-(Q2-D)") (class "Default")
      (node (ref "D3") (pin "C") (pinfunction "C_C") (pintype "passive"))
      (node (ref "Q2") (pin "3") (pinfunction "D_3") (pintype "bidirectional"))
    )
    (net (code "54") (name "Net-(Q3-D)") (class "Default")
      (node (ref "D4") (pin "C") (pinfunction "C_C") (pintype "passive"))
      (node (ref "Q3") (pin "3") (pinfunction "D_3") (pintype "bidirectional"))
    )
    (net (code "55") (name "Net-(Q4-D)") (class "Default")
      (node (ref "D1") (pin "C") (pinfunction "C_C") (pintype "passive"))
      (node (ref "Q4") (pin "3") (pinfunction "D_3") (pintype "bidirectional"))
    )
    (net (code "56") (name "PARAM[0]_5X5") (class "Default")
      (node (ref "PARAM_0_SELECT") (pin "1") (pinfunction "1_1") (pintype "passive"))
      (node (ref "SOCKET_2") (pin "28") (pinfunction "28_28") (pintype "passive"))
    )
    (net (code "57") (name "PARAM[0]_5X7.5") (class "Default")
      (node (ref "PARAM_0_SELECT") (pin "3") (pinfunction "3_3") (pintype "passive"))
      (node (ref "SOCKET_2") (pin "27") (pinfunction "27_27") (pintype "passive"))
    )
    (net (code "58") (name "QSPI_CS") (class "Default")
      (node (ref "QSPI") (pin "7") (pinfunction "7_7") (pintype "passive"))
      (node (ref "SOCKET_2") (pin "7") (pinfunction "7_7") (pintype "passive"))
    )
    (net (code "59") (name "QSPI_MISO") (class "Default")
      (node (ref "QSPI") (pin "3") (pinfunction "3_3") (pintype "passive"))
      (node (ref "SOCKET_2") (pin "10") (pinfunction "10_10") (pintype "passive"))
    )
    (net (code "60") (name "QSPI_MOSI") (class "Default")
      (node (ref "QSPI") (pin "1") (pinfunction "1_1") (pintype "passive"))
      (node (ref "SOCKET_2") (pin "11") (pinfunction "11_11") (pintype "passive"))
    )
    (net (code "61") (name "QSPI_SCK") (class "Default")
      (node (ref "QSPI") (pin "5") (pinfunction "5_5") (pintype "passive"))
      (node (ref "SOCKET_2") (pin "9") (pinfunction "9_9") (pintype "passive"))
    )
    (net (code "62") (name "RST_N") (class "Default")
      (node (ref "GPIO3") (pin "4") (pinfunction "4_4") (pintype "passive"))
      (node (ref "SOCKET_2") (pin "15") (pinfunction "15_15") (pintype "passive"))
    )
    (net (code "63") (name "RX") (class "Default")
      (node (ref "IC2") (pin "13") (pinfunction "B7_13") (pintype "bidirectional"))
      (node (ref "USB-UART_1") (pin "2") (pinfunction "2_2") (pintype "passive"))
    )
    (net (code "64") (name "SCLK") (class "Default")
      (node (ref "IC1") (pin "16") (pinfunction "B4_16") (pintype "bidirectional"))
      (node (ref "SD_CARD") (pin "6") (pinfunction "6_6") (pintype "passive"))
    )
    (net (code "65") (name "SDIO_CLK") (class "Default")
      (node (ref "SDCARD") (pin "7") (pinfunction "7_7") (pintype "passive"))
      (node (ref "SOCKET_1") (pin "31") (pinfunction "31_31") (pintype "passive"))
    )
    (net (code "66") (name "SDIO_CMD") (class "Default")
      (node (ref "SDCARD") (pin "5") (pinfunction "5_5") (pintype "passive"))
      (node (ref "SOCKET_1") (pin "32") (pinfunction "32_32") (pintype "passive"))
    )
    (net (code "67") (name "SDIO_DAT_0") (class "Default")
      (node (ref "SDCARD") (pin "3") (pinfunction "3_3") (pintype "passive"))
      (node (ref "SOCKET_2") (pin "1") (pinfunction "1_1") (pintype "passive"))
    )
    (net (code "68") (name "SDIO_DAT_3") (class "Default")
      (node (ref "SDCARD") (pin "1") (pinfunction "1_1") (pintype "passive"))
      (node (ref "SOCKET_2") (pin "2") (pinfunction "2_2") (pintype "passive"))
    )
    (net (code "69") (name "SYS_CLK") (class "Default")
      (node (ref "CLOCK") (pin "2") (pinfunction "2_2") (pintype "passive"))
      (node (ref "J4") (pin "5") (pinfunction "5_5") (pintype "bidirectional"))
      (node (ref "SOCKET_2") (pin "14") (pinfunction "14_14") (pintype "passive"))
    )
    (net (code "70") (name "TCK") (class "Default")
      (node (ref "IC1") (pin "14") (pinfunction "B6_14") (pintype "bidirectional"))
      (node (ref "JTAG_20_PIN") (pin "9") (pinfunction "9_9") (pintype "passive"))
    )
    (net (code "71") (name "TDI") (class "Default")
      (node (ref "IC1") (pin "12") (pinfunction "B8_12") (pintype "bidirectional"))
      (node (ref "JTAG_20_PIN") (pin "5") (pinfunction "5_5") (pintype "passive"))
    )
    (net (code "72") (name "TDO") (class "Default")
      (node (ref "IC1") (pin "13") (pinfunction "B7_13") (pintype "bidirectional"))
      (node (ref "JTAG_20_PIN") (pin "13") (pinfunction "13_13") (pintype "passive"))
    )
    (net (code "73") (name "TLPORT_A_BITS_ADDRESS[0]") (class "Default")
      (node (ref "GPIO1") (pin "18") (pinfunction "18_18") (pintype "passive"))
      (node (ref "SOCKET_4") (pin "23") (pinfunction "23_23") (pintype "passive"))
    )
    (net (code "74") (name "TLPORT_A_BITS_ADDRESS[1]") (class "Default")
      (node (ref "GPIO1") (pin "17") (pinfunction "17_17") (pintype "passive"))
      (node (ref "SOCKET_4") (pin "21") (pinfunction "21_21") (pintype "passive"))
    )
    (net (code "75") (name "TLPORT_A_BITS_ADDRESS[2]") (class "Default")
      (node (ref "GPIO1") (pin "16") (pinfunction "16_16") (pintype "passive"))
      (node (ref "SOCKET_4") (pin "20") (pinfunction "20_20") (pintype "passive"))
    )
    (net (code "76") (name "TLPORT_A_BITS_ADDRESS[3]") (class "Default")
      (node (ref "GPIO1") (pin "15") (pinfunction "15_15") (pintype "passive"))
      (node (ref "SOCKET_4") (pin "18") (pinfunction "18_18") (pintype "passive"))
    )
    (net (code "77") (name "TLPORT_A_BITS_ADDRESS[4]") (class "Default")
      (node (ref "GPIO1") (pin "14") (pinfunction "14_14") (pintype "passive"))
      (node (ref "SOCKET_4") (pin "17") (pinfunction "17_17") (pintype "passive"))
    )
    (net (code "78") (name "TLPORT_A_BITS_ADDRESS[5]") (class "Default")
      (node (ref "GPIO1") (pin "13") (pinfunction "13_13") (pintype "passive"))
      (node (ref "SOCKET_4") (pin "15") (pinfunction "15_15") (pintype "passive"))
    )
    (net (code "79") (name "TLPORT_A_BITS_ADDRESS[6]") (class "Default")
      (node (ref "GPIO1") (pin "10") (pinfunction "10_10") (pintype "passive"))
      (node (ref "SOCKET_4") (pin "14") (pinfunction "14_14") (pintype "passive"))
    )
    (net (code "80") (name "TLPORT_A_BITS_ADDRESS[7]") (class "Default")
      (node (ref "GPIO1") (pin "9") (pinfunction "9_9") (pintype "passive"))
      (node (ref "SOCKET_4") (pin "13") (pinfunction "13_13") (pintype "passive"))
    )
    (net (code "81") (name "TLPORT_A_BITS_ADDRESS[8]") (class "Default")
      (node (ref "GPIO1") (pin "8") (pinfunction "8_8") (pintype "passive"))
      (node (ref "SOCKET_4") (pin "12") (pinfunction "12_12") (pintype "passive"))
    )
    (net (code "82") (name "TLPORT_A_BITS_ADDRESS[9]") (class "Default")
      (node (ref "GPIO1") (pin "7") (pinfunction "7_7") (pintype "passive"))
      (node (ref "SOCKET_4") (pin "11") (pinfunction "11_11") (pintype "passive"))
    )
    (net (code "83") (name "TLPORT_A_BITS_ADDRESS[10]") (class "Default")
      (node (ref "GPIO1") (pin "6") (pinfunction "6_6") (pintype "passive"))
      (node (ref "SOCKET_4") (pin "10") (pinfunction "10_10") (pintype "passive"))
    )
    (net (code "84") (name "TLPORT_A_BITS_ADDRESS[11]") (class "Default")
      (node (ref "GPIO1") (pin "5") (pinfunction "5_5") (pintype "passive"))
      (node (ref "SOCKET_4") (pin "9") (pinfunction "9_9") (pintype "passive"))
    )
    (net (code "85") (name "TLPORT_A_BITS_ADDRESS[12]") (class "Default")
      (node (ref "GPIO1") (pin "4") (pinfunction "4_4") (pintype "passive"))
      (node (ref "SOCKET_4") (pin "7") (pinfunction "7_7") (pintype "passive"))
    )
    (net (code "86") (name "TLPORT_A_BITS_ADDRESS[13]") (class "Default")
      (node (ref "GPIO1") (pin "3") (pinfunction "3_3") (pintype "passive"))
      (node (ref "SOCKET_4") (pin "6") (pinfunction "6_6") (pintype "passive"))
    )
    (net (code "87") (name "TLPORT_A_BITS_ADDRESS[14]") (class "Default")
      (node (ref "GPIO1") (pin "2") (pinfunction "2_2") (pintype "passive"))
      (node (ref "SOCKET_4") (pin "5") (pinfunction "5_5") (pintype "passive"))
    )
    (net (code "88") (name "TLPORT_A_BITS_ADDRESS[15]") (class "Default")
      (node (ref "GPIO1") (pin "1") (pinfunction "1_1") (pintype "passive"))
      (node (ref "SOCKET_4") (pin "4") (pinfunction "4_4") (pintype "passive"))
    )
    (net (code "89") (name "TLPORT_A_BITS_ADDRESS[16]") (class "Default")
      (node (ref "GPIO3") (pin "40") (pinfunction "40_40") (pintype "passive"))
      (node (ref "SOCKET_4") (pin "3") (pinfunction "3_3") (pintype "passive"))
    )
    (net (code "90") (name "TLPORT_A_BITS_ADDRESS[17]") (class "Default")
      (node (ref "GPIO3") (pin "39") (pinfunction "39_39") (pintype "passive"))
      (node (ref "SOCKET_4") (pin "2") (pinfunction "2_2") (pintype "passive"))
    )
    (net (code "91") (name "TLPORT_A_BITS_ADDRESS[18]") (class "Default")
      (node (ref "GPIO3") (pin "38") (pinfunction "38_38") (pintype "passive"))
      (node (ref "SOCKET_4") (pin "1") (pinfunction "1_1") (pintype "passive"))
    )
    (net (code "92") (name "TLPORT_A_BITS_ADDRESS[19]") (class "Default")
      (node (ref "GPIO3") (pin "37") (pinfunction "37_37") (pintype "passive"))
      (node (ref "SOCKET_3") (pin "32") (pinfunction "32_32") (pintype "passive"))
    )
    (net (code "93") (name "TLPORT_A_BITS_ADDRESS[20]") (class "Default")
      (node (ref "GPIO3") (pin "36") (pinfunction "36_36") (pintype "passive"))
      (node (ref "SOCKET_3") (pin "31") (pinfunction "31_31") (pintype "passive"))
    )
    (net (code "94") (name "TLPORT_A_BITS_ADDRESS[21]") (class "Default")
      (node (ref "GPIO3") (pin "35") (pinfunction "35_35") (pintype "passive"))
      (node (ref "SOCKET_3") (pin "29") (pinfunction "29_29") (pintype "passive"))
    )
    (net (code "95") (name "TLPORT_A_BITS_ADDRESS[22]") (class "Default")
      (node (ref "GPIO3") (pin "34") (pinfunction "34_34") (pintype "passive"))
      (node (ref "SOCKET_3") (pin "28") (pinfunction "28_28") (pintype "passive"))
    )
    (net (code "96") (name "TLPORT_A_BITS_ADDRESS[23]") (class "Default")
      (node (ref "GPIO3") (pin "33") (pinfunction "33_33") (pintype "passive"))
      (node (ref "SOCKET_3") (pin "27") (pinfunction "27_27") (pintype "passive"))
    )
    (net (code "97") (name "TLPORT_A_BITS_ADDRESS[24]") (class "Default")
      (node (ref "GPIO3") (pin "32") (pinfunction "32_32") (pintype "passive"))
      (node (ref "SOCKET_3") (pin "26") (pinfunction "26_26") (pintype "passive"))
    )
    (net (code "98") (name "TLPORT_A_BITS_ADDRESS[25]") (class "Default")
      (node (ref "GPIO3") (pin "31") (pinfunction "31_31") (pintype "passive"))
      (node (ref "SOCKET_3") (pin "25") (pinfunction "25_25") (pintype "passive"))
    )
    (net (code "99") (name "TLPORT_A_BITS_ADDRESS[26]") (class "Default")
      (node (ref "GPIO3") (pin "28") (pinfunction "28_28") (pintype "passive"))
      (node (ref "SOCKET_3") (pin "23") (pinfunction "23_23") (pintype "passive"))
    )
    (net (code "100") (name "TLPORT_A_BITS_ADDRESS[27]") (class "Default")
      (node (ref "GPIO3") (pin "27") (pinfunction "27_27") (pintype "passive"))
      (node (ref "SOCKET_3") (pin "22") (pinfunction "22_22") (pintype "passive"))
    )
    (net (code "101") (name "TLPORT_A_BITS_ADDRESS[28]") (class "Default")
      (node (ref "GPIO3") (pin "26") (pinfunction "26_26") (pintype "passive"))
      (node (ref "SOCKET_3") (pin "21") (pinfunction "21_21") (pintype "passive"))
    )
    (net (code "102") (name "TLPORT_A_BITS_ADDRESS[29]") (class "Default")
      (node (ref "GPIO3") (pin "25") (pinfunction "25_25") (pintype "passive"))
      (node (ref "SOCKET_3") (pin "20") (pinfunction "20_20") (pintype "passive"))
    )
    (net (code "103") (name "TLPORT_A_BITS_ADDRESS[30]") (class "Default")
      (node (ref "GPIO3") (pin "24") (pinfunction "24_24") (pintype "passive"))
      (node (ref "SOCKET_3") (pin "19") (pinfunction "19_19") (pintype "passive"))
    )
    (net (code "104") (name "TLPORT_A_BITS_ADDRESS[31]") (class "Default")
      (node (ref "GPIO3") (pin "23") (pinfunction "23_23") (pintype "passive"))
      (node (ref "SOCKET_3") (pin "18") (pinfunction "18_18") (pintype "passive"))
    )
    (net (code "105") (name "TLPORT_A_BITS_CORRUPT") (class "Default")
      (node (ref "GPIO0") (pin "19") (pinfunction "19_19") (pintype "passive"))
      (node (ref "SOCKET_6") (pin "14") (pinfunction "14_14") (pintype "passive"))
    )
    (net (code "106") (name "TLPORT_A_BITS_DATA[0]") (class "Default")
      (node (ref "GPIO0") (pin "18") (pinfunction "18_18") (pintype "passive"))
      (node (ref "SOCKET_6") (pin "13") (pinfunction "13_13") (pintype "passive"))
    )
    (net (code "107") (name "TLPORT_A_BITS_DATA[1]") (class "Default")
      (node (ref "GPIO0") (pin "17") (pinfunction "17_17") (pintype "passive"))
      (node (ref "SOCKET_6") (pin "12") (pinfunction "12_12") (pintype "passive"))
    )
    (net (code "108") (name "TLPORT_A_BITS_DATA[2]") (class "Default")
      (node (ref "GPIO0") (pin "16") (pinfunction "16_16") (pintype "passive"))
      (node (ref "SOCKET_6") (pin "11") (pinfunction "11_11") (pintype "passive"))
    )
    (net (code "109") (name "TLPORT_A_BITS_DATA[3]") (class "Default")
      (node (ref "GPIO0") (pin "15") (pinfunction "15_15") (pintype "passive"))
      (node (ref "SOCKET_6") (pin "10") (pinfunction "10_10") (pintype "passive"))
    )
    (net (code "110") (name "TLPORT_A_BITS_DATA[4]") (class "Default")
      (node (ref "GPIO0") (pin "14") (pinfunction "14_14") (pintype "passive"))
      (node (ref "SOCKET_6") (pin "9") (pinfunction "9_9") (pintype "passive"))
    )
    (net (code "111") (name "TLPORT_A_BITS_DATA[5]") (class "Default")
      (node (ref "GPIO0") (pin "13") (pinfunction "13_13") (pintype "passive"))
      (node (ref "SOCKET_6") (pin "7") (pinfunction "7_7") (pintype "passive"))
    )
    (net (code "112") (name "TLPORT_A_BITS_DATA[6]") (class "Default")
      (node (ref "GPIO0") (pin "10") (pinfunction "10_10") (pintype "passive"))
      (node (ref "SOCKET_6") (pin "6") (pinfunction "6_6") (pintype "passive"))
    )
    (net (code "113") (name "TLPORT_A_BITS_DATA[7]") (class "Default")
      (node (ref "GPIO0") (pin "9") (pinfunction "9_9") (pintype "passive"))
      (node (ref "SOCKET_6") (pin "5") (pinfunction "5_5") (pintype "passive"))
    )
    (net (code "114") (name "TLPORT_A_BITS_DATA[8]") (class "Default")
      (node (ref "GPIO0") (pin "8") (pinfunction "8_8") (pintype "passive"))
      (node (ref "SOCKET_6") (pin "4") (pinfunction "4_4") (pintype "passive"))
    )
    (net (code "115") (name "TLPORT_A_BITS_DATA[9]") (class "Default")
      (node (ref "GPIO0") (pin "7") (pinfunction "7_7") (pintype "passive"))
      (node (ref "SOCKET_6") (pin "3") (pinfunction "3_3") (pintype "passive"))
    )
    (net (code "116") (name "TLPORT_A_BITS_DATA[10]") (class "Default")
      (node (ref "GPIO0") (pin "6") (pinfunction "6_6") (pintype "passive"))
      (node (ref "SOCKET_6") (pin "2") (pinfunction "2_2") (pintype "passive"))
    )
    (net (code "117") (name "TLPORT_A_BITS_DATA[11]") (class "Default")
      (node (ref "GPIO0") (pin "5") (pinfunction "5_5") (pintype "passive"))
      (node (ref "SOCKET_6") (pin "1") (pinfunction "1_1") (pintype "passive"))
    )
    (net (code "118") (name "TLPORT_A_BITS_DATA[12]") (class "Default")
      (node (ref "GPIO0") (pin "4") (pinfunction "4_4") (pintype "passive"))
      (node (ref "SOCKET_5") (pin "32") (pinfunction "32_32") (pintype "passive"))
    )
    (net (code "119") (name "TLPORT_A_BITS_DATA[13]") (class "Default")
      (node (ref "GPIO0") (pin "3") (pinfunction "3_3") (pintype "passive"))
      (node (ref "SOCKET_5") (pin "31") (pinfunction "31_31") (pintype "passive"))
    )
    (net (code "120") (name "TLPORT_A_BITS_DATA[14]") (class "Default")
      (node (ref "GPIO0") (pin "2") (pinfunction "2_2") (pintype "passive"))
      (node (ref "SOCKET_5") (pin "29") (pinfunction "29_29") (pintype "passive"))
    )
    (net (code "121") (name "TLPORT_A_BITS_DATA[15]") (class "Default")
      (node (ref "GPIO0") (pin "1") (pinfunction "1_1") (pintype "passive"))
      (node (ref "SOCKET_5") (pin "28") (pinfunction "28_28") (pintype "passive"))
    )
    (net (code "122") (name "TLPORT_A_BITS_DATA[16]") (class "Default")
      (node (ref "GPIO1") (pin "39") (pinfunction "39_39") (pintype "passive"))
      (node (ref "SOCKET_5") (pin "27") (pinfunction "27_27") (pintype "passive"))
    )
    (net (code "123") (name "TLPORT_A_BITS_DATA[17]") (class "Default")
      (node (ref "GPIO1") (pin "37") (pinfunction "37_37") (pintype "passive"))
      (node (ref "SOCKET_5") (pin "26") (pinfunction "26_26") (pintype "passive"))
    )
    (net (code "124") (name "TLPORT_A_BITS_DATA[18]") (class "Default")
      (node (ref "GPIO1") (pin "40") (pinfunction "40_40") (pintype "passive"))
      (node (ref "SOCKET_5") (pin "25") (pinfunction "25_25") (pintype "passive"))
    )
    (net (code "125") (name "TLPORT_A_BITS_DATA[19]") (class "Default")
      (node (ref "GPIO1") (pin "38") (pinfunction "38_38") (pintype "passive"))
      (node (ref "SOCKET_5") (pin "23") (pinfunction "23_23") (pintype "passive"))
    )
    (net (code "126") (name "TLPORT_A_BITS_DATA[20]") (class "Default")
      (node (ref "GPIO1") (pin "36") (pinfunction "36_36") (pintype "passive"))
      (node (ref "SOCKET_5") (pin "22") (pinfunction "22_22") (pintype "passive"))
    )
    (net (code "127") (name "TLPORT_A_BITS_DATA[21]") (class "Default")
      (node (ref "GPIO1") (pin "35") (pinfunction "35_35") (pintype "passive"))
      (node (ref "SOCKET_5") (pin "21") (pinfunction "21_21") (pintype "passive"))
    )
    (net (code "128") (name "TLPORT_A_BITS_DATA[22]") (class "Default")
      (node (ref "GPIO1") (pin "34") (pinfunction "34_34") (pintype "passive"))
      (node (ref "SOCKET_5") (pin "20") (pinfunction "20_20") (pintype "passive"))
    )
    (net (code "129") (name "TLPORT_A_BITS_DATA[23]") (class "Default")
      (node (ref "GPIO1") (pin "33") (pinfunction "33_33") (pintype "passive"))
      (node (ref "SOCKET_5") (pin "19") (pinfunction "19_19") (pintype "passive"))
    )
    (net (code "130") (name "TLPORT_A_BITS_DATA[24]") (class "Default")
      (node (ref "GPIO1") (pin "32") (pinfunction "32_32") (pintype "passive"))
      (node (ref "SOCKET_5") (pin "18") (pinfunction "18_18") (pintype "passive"))
    )
    (net (code "131") (name "TLPORT_A_BITS_DATA[25]") (class "Default")
      (node (ref "GPIO1") (pin "31") (pinfunction "31_31") (pintype "passive"))
      (node (ref "SOCKET_5") (pin "17") (pinfunction "17_17") (pintype "passive"))
    )
    (net (code "132") (name "TLPORT_A_BITS_DATA[26]") (class "Default")
      (node (ref "GPIO1") (pin "27") (pinfunction "27_27") (pintype "passive"))
      (node (ref "SOCKET_5") (pin "15") (pinfunction "15_15") (pintype "passive"))
    )
    (net (code "133") (name "TLPORT_A_BITS_DATA[27]") (class "Default")
      (node (ref "GPIO1") (pin "25") (pinfunction "25_25") (pintype "passive"))
      (node (ref "SOCKET_5") (pin "14") (pinfunction "14_14") (pintype "passive"))
    )
    (net (code "134") (name "TLPORT_A_BITS_DATA[28]") (class "Default")
      (node (ref "GPIO1") (pin "28") (pinfunction "28_28") (pintype "passive"))
      (node (ref "SOCKET_5") (pin "13") (pinfunction "13_13") (pintype "passive"))
    )
    (net (code "135") (name "TLPORT_A_BITS_DATA[29]") (class "Default")
      (node (ref "GPIO1") (pin "26") (pinfunction "26_26") (pintype "passive"))
      (node (ref "SOCKET_5") (pin "12") (pinfunction "12_12") (pintype "passive"))
    )
    (net (code "136") (name "TLPORT_A_BITS_DATA[30]") (class "Default")
      (node (ref "GPIO1") (pin "24") (pinfunction "24_24") (pintype "passive"))
      (node (ref "SOCKET_5") (pin "10") (pinfunction "10_10") (pintype "passive"))
    )
    (net (code "137") (name "TLPORT_A_BITS_DATA[31]") (class "Default")
      (node (ref "GPIO1") (pin "23") (pinfunction "23_23") (pintype "passive"))
      (node (ref "SOCKET_5") (pin "9") (pinfunction "9_9") (pintype "passive"))
    )
    (net (code "138") (name "TLPORT_A_BITS_MASK[0]") (class "Default")
      (node (ref "GPIO1") (pin "22") (pinfunction "22_22") (pintype "passive"))
      (node (ref "SOCKET_5") (pin "8") (pinfunction "8_8") (pintype "passive"))
    )
    (net (code "139") (name "TLPORT_A_BITS_MASK[1]") (class "Default")
      (node (ref "GPIO1") (pin "21") (pinfunction "21_21") (pintype "passive"))
      (node (ref "SOCKET_5") (pin "7") (pinfunction "7_7") (pintype "passive"))
    )
    (net (code "140") (name "TLPORT_A_BITS_MASK[2]") (class "Default")
      (node (ref "GPIO1") (pin "20") (pinfunction "20_20") (pintype "passive"))
      (node (ref "SOCKET_4") (pin "25") (pinfunction "25_25") (pintype "passive"))
    )
    (net (code "141") (name "TLPORT_A_BITS_MASK[3]") (class "Default")
      (node (ref "GPIO1") (pin "19") (pinfunction "19_19") (pintype "passive"))
      (node (ref "SOCKET_4") (pin "24") (pinfunction "24_24") (pintype "passive"))
    )
    (net (code "142") (name "TLPORT_A_BITS_OPCODE[0]") (class "Default")
      (node (ref "GPIO3") (pin "8") (pinfunction "8_8") (pintype "passive"))
      (node (ref "SOCKET_2") (pin "24") (pinfunction "24_24") (pintype "passive"))
    )
    (net (code "143") (name "TLPORT_A_BITS_OPCODE[1]") (class "Default")
      (node (ref "GPIO3") (pin "7") (pinfunction "7_7") (pintype "passive"))
      (node (ref "SOCKET_2") (pin "23") (pinfunction "23_23") (pintype "passive"))
    )
    (net (code "144") (name "TLPORT_A_BITS_OPCODE[2]") (class "Default")
      (node (ref "GPIO3") (pin "3") (pinfunction "3_3") (pintype "passive"))
      (node (ref "SOCKET_2") (pin "21") (pinfunction "21_21") (pintype "passive"))
    )
    (net (code "145") (name "TLPORT_A_BITS_PARAM[0]") (class "Default")
      (node (ref "GPIO3") (pin "13") (pinfunction "13_13") (pintype "passive"))
      (node (ref "PARAM_0_SELECT") (pin "2") (pinfunction "2_2") (pintype "passive"))
      (node (ref "PARAM_0_SELECT") (pin "4") (pinfunction "4_4") (pintype "passive"))
    )
    (net (code "146") (name "TLPORT_A_BITS_PARAM[1]") (class "Default")
      (node (ref "GPIO3") (pin "10") (pinfunction "10_10") (pintype "passive"))
      (node (ref "SOCKET_2") (pin "26") (pinfunction "26_26") (pintype "passive"))
    )
    (net (code "147") (name "TLPORT_A_BITS_PARAM[2]") (class "Default")
      (node (ref "GPIO3") (pin "9") (pinfunction "9_9") (pintype "passive"))
      (node (ref "SOCKET_2") (pin "25") (pinfunction "25_25") (pintype "passive"))
    )
    (net (code "148") (name "TLPORT_A_BITS_SIZE[0]") (class "Default")
      (node (ref "GPIO3") (pin "16") (pinfunction "16_16") (pintype "passive"))
      (node (ref "SOCKET_3") (pin "9") (pinfunction "9_9") (pintype "passive"))
    )
    (net (code "149") (name "TLPORT_A_BITS_SIZE[1]") (class "Default")
      (node (ref "GPIO3") (pin "15") (pinfunction "15_15") (pintype "passive"))
      (node (ref "SOCKET_3") (pin "8") (pinfunction "8_8") (pintype "passive"))
    )
    (net (code "150") (name "TLPORT_A_BITS_SIZE[2]") (class "Default")
      (node (ref "GPIO3") (pin "14") (pinfunction "14_14") (pintype "passive"))
      (node (ref "SOCKET_3") (pin "7") (pinfunction "7_7") (pintype "passive"))
    )
    (net (code "151") (name "TLPORT_A_BITS_SOURCE[0]") (class "Default")
      (node (ref "GPIO3") (pin "22") (pinfunction "22_22") (pintype "passive"))
      (node (ref "SOCKET_3") (pin "17") (pinfunction "17_17") (pintype "passive"))
    )
    (net (code "152") (name "TLPORT_A_BITS_SOURCE[1]") (class "Default")
      (node (ref "GPIO3") (pin "21") (pinfunction "21_21") (pintype "passive"))
      (node (ref "SOCKET_3") (pin "15") (pinfunction "15_15") (pintype "passive"))
    )
    (net (code "153") (name "TLPORT_A_BITS_SOURCE[2]") (class "Default")
      (node (ref "GPIO3") (pin "20") (pinfunction "20_20") (pintype "passive"))
      (node (ref "SOCKET_3") (pin "14") (pinfunction "14_14") (pintype "passive"))
    )
    (net (code "154") (name "TLPORT_A_BITS_SOURCE[3]") (class "Default")
      (node (ref "GPIO3") (pin "19") (pinfunction "19_19") (pintype "passive"))
      (node (ref "SOCKET_3") (pin "13") (pinfunction "13_13") (pintype "passive"))
    )
    (net (code "155") (name "TLPORT_A_BITS_SOURCE[4]") (class "Default")
      (node (ref "GPIO3") (pin "18") (pinfunction "18_18") (pintype "passive"))
      (node (ref "SOCKET_3") (pin "12") (pinfunction "12_12") (pintype "passive"))
    )
    (net (code "156") (name "TLPORT_A_BITS_SOURCE[5]") (class "Default")
      (node (ref "GPIO3") (pin "17") (pinfunction "17_17") (pintype "passive"))
      (node (ref "SOCKET_3") (pin "10") (pinfunction "10_10") (pintype "passive"))
    )
    (net (code "157") (name "TLPORT_A_READY") (class "Default")
      (node (ref "GPIO3") (pin "6") (pinfunction "6_6") (pintype "passive"))
      (node (ref "SOCKET_2") (pin "18") (pinfunction "18_18") (pintype "passive"))
    )
    (net (code "158") (name "TLPORT_A_VALID") (class "Default")
      (node (ref "GPIO3") (pin "1") (pinfunction "1_1") (pintype "passive"))
      (node (ref "SOCKET_2") (pin "20") (pinfunction "20_20") (pintype "passive"))
    )
    (net (code "159") (name "TLPORT_D_BITS_CORRUPT") (class "Default")
      (node (ref "GPIO0") (pin "28") (pinfunction "28_28") (pintype "passive"))
      (node (ref "SOCKET_7") (pin "19") (pinfunction "19_19") (pintype "passive"))
    )
    (net (code "160") (name "TLPORT_D_BITS_DATA[0]") (class "Default")
      (node (ref "GPIO2") (pin "40") (pinfunction "40_40") (pintype "passive"))
      (node (ref "SOCKET_8") (pin "25") (pinfunction "25_25") (pintype "passive"))
    )
    (net (code "161") (name "TLPORT_D_BITS_DATA[1]") (class "Default")
      (node (ref "GPIO2") (pin "39") (pinfunction "39_39") (pintype "passive"))
      (node (ref "SOCKET_8") (pin "24") (pinfunction "24_24") (pintype "passive"))
    )
    (net (code "162") (name "TLPORT_D_BITS_DATA[2]") (class "Default")
      (node (ref "GPIO2") (pin "38") (pinfunction "38_38") (pintype "passive"))
      (node (ref "SOCKET_8") (pin "23") (pinfunction "23_23") (pintype "passive"))
    )
    (net (code "163") (name "TLPORT_D_BITS_DATA[3]") (class "Default")
      (node (ref "GPIO2") (pin "37") (pinfunction "37_37") (pintype "passive"))
      (node (ref "SOCKET_8") (pin "21") (pinfunction "21_21") (pintype "passive"))
    )
    (net (code "164") (name "TLPORT_D_BITS_DATA[4]") (class "Default")
      (node (ref "GPIO2") (pin "36") (pinfunction "36_36") (pintype "passive"))
      (node (ref "SOCKET_8") (pin "20") (pinfunction "20_20") (pintype "passive"))
    )
    (net (code "165") (name "TLPORT_D_BITS_DATA[5]") (class "Default")
      (node (ref "GPIO2") (pin "35") (pinfunction "35_35") (pintype "passive"))
      (node (ref "SOCKET_8") (pin "18") (pinfunction "18_18") (pintype "passive"))
    )
    (net (code "166") (name "TLPORT_D_BITS_DATA[6]") (class "Default")
      (node (ref "GPIO2") (pin "34") (pinfunction "34_34") (pintype "passive"))
      (node (ref "SOCKET_8") (pin "17") (pinfunction "17_17") (pintype "passive"))
    )
    (net (code "167") (name "TLPORT_D_BITS_DATA[7]") (class "Default")
      (node (ref "GPIO2") (pin "33") (pinfunction "33_33") (pintype "passive"))
      (node (ref "SOCKET_8") (pin "15") (pinfunction "15_15") (pintype "passive"))
    )
    (net (code "168") (name "TLPORT_D_BITS_DATA[8]") (class "Default")
      (node (ref "GPIO2") (pin "32") (pinfunction "32_32") (pintype "passive"))
      (node (ref "SOCKET_8") (pin "14") (pinfunction "14_14") (pintype "passive"))
    )
    (net (code "169") (name "TLPORT_D_BITS_DATA[9]") (class "Default")
      (node (ref "GPIO2") (pin "31") (pinfunction "31_31") (pintype "passive"))
      (node (ref "SOCKET_8") (pin "13") (pinfunction "13_13") (pintype "passive"))
    )
    (net (code "170") (name "TLPORT_D_BITS_DATA[10]") (class "Default")
      (node (ref "GPIO2") (pin "28") (pinfunction "28_28") (pintype "passive"))
      (node (ref "SOCKET_8") (pin "12") (pinfunction "12_12") (pintype "passive"))
    )
    (net (code "171") (name "TLPORT_D_BITS_DATA[11]") (class "Default")
      (node (ref "GPIO2") (pin "27") (pinfunction "27_27") (pintype "passive"))
      (node (ref "SOCKET_8") (pin "11") (pinfunction "11_11") (pintype "passive"))
    )
    (net (code "172") (name "TLPORT_D_BITS_DATA[12]") (class "Default")
      (node (ref "GPIO2") (pin "26") (pinfunction "26_26") (pintype "passive"))
      (node (ref "SOCKET_8") (pin "10") (pinfunction "10_10") (pintype "passive"))
    )
    (net (code "173") (name "TLPORT_D_BITS_DATA[13]") (class "Default")
      (node (ref "GPIO2") (pin "25") (pinfunction "25_25") (pintype "passive"))
      (node (ref "SOCKET_8") (pin "9") (pinfunction "9_9") (pintype "passive"))
    )
    (net (code "174") (name "TLPORT_D_BITS_DATA[14]") (class "Default")
      (node (ref "GPIO2") (pin "24") (pinfunction "24_24") (pintype "passive"))
      (node (ref "SOCKET_8") (pin "7") (pinfunction "7_7") (pintype "passive"))
    )
    (net (code "175") (name "TLPORT_D_BITS_DATA[15]") (class "Default")
      (node (ref "GPIO2") (pin "23") (pinfunction "23_23") (pintype "passive"))
      (node (ref "SOCKET_8") (pin "6") (pinfunction "6_6") (pintype "passive"))
    )
    (net (code "176") (name "TLPORT_D_BITS_DATA[16]") (class "Default")
      (node (ref "GPIO2") (pin "22") (pinfunction "22_22") (pintype "passive"))
      (node (ref "SOCKET_8") (pin "5") (pinfunction "5_5") (pintype "passive"))
    )
    (net (code "177") (name "TLPORT_D_BITS_DATA[17]") (class "Default")
      (node (ref "GPIO2") (pin "21") (pinfunction "21_21") (pintype "passive"))
      (node (ref "SOCKET_8") (pin "4") (pinfunction "4_4") (pintype "passive"))
    )
    (net (code "178") (name "TLPORT_D_BITS_DATA[18]") (class "Default")
      (node (ref "GPIO2") (pin "20") (pinfunction "20_20") (pintype "passive"))
      (node (ref "SOCKET_8") (pin "3") (pinfunction "3_3") (pintype "passive"))
    )
    (net (code "179") (name "TLPORT_D_BITS_DATA[19]") (class "Default")
      (node (ref "GPIO2") (pin "19") (pinfunction "19_19") (pintype "passive"))
      (node (ref "SOCKET_8") (pin "2") (pinfunction "2_2") (pintype "passive"))
    )
    (net (code "180") (name "TLPORT_D_BITS_DATA[20]") (class "Default")
      (node (ref "GPIO2") (pin "18") (pinfunction "18_18") (pintype "passive"))
      (node (ref "SOCKET_8") (pin "1") (pinfunction "1_1") (pintype "passive"))
    )
    (net (code "181") (name "TLPORT_D_BITS_DATA[21]") (class "Default")
      (node (ref "GPIO2") (pin "17") (pinfunction "17_17") (pintype "passive"))
      (node (ref "SOCKET_7") (pin "32") (pinfunction "32_32") (pintype "passive"))
    )
    (net (code "182") (name "TLPORT_D_BITS_DATA[22]") (class "Default")
      (node (ref "GPIO2") (pin "16") (pinfunction "16_16") (pintype "passive"))
      (node (ref "SOCKET_7") (pin "31") (pinfunction "31_31") (pintype "passive"))
    )
    (net (code "183") (name "TLPORT_D_BITS_DATA[23]") (class "Default")
      (node (ref "GPIO2") (pin "15") (pinfunction "15_15") (pintype "passive"))
      (node (ref "SOCKET_7") (pin "29") (pinfunction "29_29") (pintype "passive"))
    )
    (net (code "184") (name "TLPORT_D_BITS_DATA[24]") (class "Default")
      (node (ref "GPIO2") (pin "14") (pinfunction "14_14") (pintype "passive"))
      (node (ref "SOCKET_7") (pin "28") (pinfunction "28_28") (pintype "passive"))
    )
    (net (code "185") (name "TLPORT_D_BITS_DATA[25]") (class "Default")
      (node (ref "GPIO2") (pin "13") (pinfunction "13_13") (pintype "passive"))
      (node (ref "SOCKET_7") (pin "27") (pinfunction "27_27") (pintype "passive"))
    )
    (net (code "186") (name "TLPORT_D_BITS_DATA[26]") (class "Default")
      (node (ref "GPIO2") (pin "10") (pinfunction "10_10") (pintype "passive"))
      (node (ref "SOCKET_7") (pin "26") (pinfunction "26_26") (pintype "passive"))
    )
    (net (code "187") (name "TLPORT_D_BITS_DATA[27]") (class "Default")
      (node (ref "GPIO2") (pin "9") (pinfunction "9_9") (pintype "passive"))
      (node (ref "SOCKET_7") (pin "25") (pinfunction "25_25") (pintype "passive"))
    )
    (net (code "188") (name "TLPORT_D_BITS_DATA[28]") (class "Default")
      (node (ref "GPIO2") (pin "8") (pinfunction "8_8") (pintype "passive"))
      (node (ref "SOCKET_7") (pin "23") (pinfunction "23_23") (pintype "passive"))
    )
    (net (code "189") (name "TLPORT_D_BITS_DATA[29]") (class "Default")
      (node (ref "GPIO2") (pin "7") (pinfunction "7_7") (pintype "passive"))
      (node (ref "SOCKET_7") (pin "22") (pinfunction "22_22") (pintype "passive"))
    )
    (net (code "190") (name "TLPORT_D_BITS_DATA[30]") (class "Default")
      (node (ref "GPIO2") (pin "6") (pinfunction "6_6") (pintype "passive"))
      (node (ref "SOCKET_7") (pin "21") (pinfunction "21_21") (pintype "passive"))
    )
    (net (code "191") (name "TLPORT_D_BITS_DATA[31]") (class "Default")
      (node (ref "GPIO2") (pin "5") (pinfunction "5_5") (pintype "passive"))
      (node (ref "SOCKET_7") (pin "20") (pinfunction "20_20") (pintype "passive"))
    )
    (net (code "192") (name "TLPORT_D_BITS_DENIED") (class "Default")
      (node (ref "GPIO0") (pin "31") (pinfunction "31_31") (pintype "passive"))
      (node (ref "SOCKET_7") (pin "18") (pinfunction "18_18") (pintype "passive"))
    )
    (net (code "193") (name "TLPORT_D_BITS_OPCODE[0]") (class "Default")
      (node (ref "GPIO0") (pin "24") (pinfunction "24_24") (pintype "passive"))
      (node (ref "SOCKET_6") (pin "21") (pinfunction "21_21") (pintype "passive"))
    )
    (net (code "194") (name "TLPORT_D_BITS_OPCODE[1]") (class "Default")
      (node (ref "GPIO0") (pin "23") (pinfunction "23_23") (pintype "passive"))
      (node (ref "SOCKET_6") (pin "20") (pinfunction "20_20") (pintype "passive"))
    )
    (net (code "195") (name "TLPORT_D_BITS_OPCODE[2]") (class "Default")
      (node (ref "GPIO0") (pin "22") (pinfunction "22_22") (pintype "passive"))
      (node (ref "SOCKET_6") (pin "18") (pinfunction "18_18") (pintype "passive"))
    )
    (net (code "196") (name "TLPORT_D_BITS_PARAM[0]") (class "Default")
      (node (ref "GPIO0") (pin "26") (pinfunction "26_26") (pintype "passive"))
      (node (ref "SOCKET_6") (pin "24") (pinfunction "24_24") (pintype "passive"))
    )
    (net (code "197") (name "TLPORT_D_BITS_PARAM[1]") (class "Default")
      (node (ref "GPIO0") (pin "25") (pinfunction "25_25") (pintype "passive"))
      (node (ref "SOCKET_6") (pin "23") (pinfunction "23_23") (pintype "passive"))
    )
    (net (code "198") (name "TLPORT_D_BITS_SINK") (class "Default")
      (node (ref "GPIO0") (pin "32") (pinfunction "32_32") (pintype "passive"))
      (node (ref "SOCKET_7") (pin "17") (pinfunction "17_17") (pintype "passive"))
    )
    (net (code "199") (name "TLPORT_D_BITS_SIZE[0]") (class "Default")
      (node (ref "GPIO0") (pin "39") (pinfunction "39_39") (pintype "passive"))
      (node (ref "SOCKET_7") (pin "8") (pinfunction "8_8") (pintype "passive"))
    )
    (net (code "200") (name "TLPORT_D_BITS_SIZE[1]") (class "Default")
      (node (ref "GPIO0") (pin "40") (pinfunction "40_40") (pintype "passive"))
      (node (ref "SOCKET_7") (pin "7") (pinfunction "7_7") (pintype "passive"))
    )
    (net (code "201") (name "TLPORT_D_BITS_SIZE[2]") (class "Default")
      (node (ref "GPIO0") (pin "27") (pinfunction "27_27") (pintype "passive"))
      (node (ref "SOCKET_6") (pin "25") (pinfunction "25_25") (pintype "passive"))
    )
    (net (code "202") (name "TLPORT_D_BITS_SOURCE[0]") (class "Default")
      (node (ref "GPIO0") (pin "33") (pinfunction "33_33") (pintype "passive"))
      (node (ref "SOCKET_7") (pin "15") (pinfunction "15_15") (pintype "passive"))
    )
    (net (code "203") (name "TLPORT_D_BITS_SOURCE[1]") (class "Default")
      (node (ref "GPIO0") (pin "34") (pinfunction "34_34") (pintype "passive"))
      (node (ref "SOCKET_7") (pin "14") (pinfunction "14_14") (pintype "passive"))
    )
    (net (code "204") (name "TLPORT_D_BITS_SOURCE[2]") (class "Default")
      (node (ref "GPIO0") (pin "35") (pinfunction "35_35") (pintype "passive"))
      (node (ref "SOCKET_7") (pin "13") (pinfunction "13_13") (pintype "passive"))
    )
    (net (code "205") (name "TLPORT_D_BITS_SOURCE[3]") (class "Default")
      (node (ref "GPIO0") (pin "36") (pinfunction "36_36") (pintype "passive"))
      (node (ref "SOCKET_7") (pin "12") (pinfunction "12_12") (pintype "passive"))
    )
    (net (code "206") (name "TLPORT_D_BITS_SOURCE[4]") (class "Default")
      (node (ref "GPIO0") (pin "38") (pinfunction "38_38") (pintype "passive"))
      (node (ref "SOCKET_7") (pin "10") (pinfunction "10_10") (pintype "passive"))
    )
    (net (code "207") (name "TLPORT_D_BITS_SOURCE[5]") (class "Default")
      (node (ref "GPIO0") (pin "37") (pinfunction "37_37") (pintype "passive"))
      (node (ref "SOCKET_7") (pin "9") (pinfunction "9_9") (pintype "passive"))
    )
    (net (code "208") (name "TLPORT_D_READY") (class "Default")
      (node (ref "GPIO0") (pin "20") (pinfunction "20_20") (pintype "passive"))
      (node (ref "SOCKET_6") (pin "15") (pinfunction "15_15") (pintype "passive"))
    )
    (net (code "209") (name "TLPORT_D_VALID") (class "Default")
      (node (ref "GPIO0") (pin "21") (pinfunction "21_21") (pintype "passive"))
      (node (ref "SOCKET_6") (pin "17") (pinfunction "17_17") (pintype "passive"))
    )
    (net (code "210") (name "TMS") (class "Default")
      (node (ref "IC1") (pin "15") (pinfunction "B5_15") (pintype "bidirectional"))
      (node (ref "JTAG_20_PIN") (pin "7") (pinfunction "7_7") (pintype "passive"))
    )
    (net (code "211") (name "TX") (class "Default")
      (node (ref "IC2") (pin "12") (pinfunction "B8_12") (pintype "bidirectional"))
      (node (ref "USB-UART_1") (pin "4") (pinfunction "4_4") (pintype "passive"))
    )
    (net (code "212") (name "UART_RXD") (class "Default")
      (node (ref "SOCKET_2") (pin "4") (pinfunction "4_4") (pintype "passive"))
      (node (ref "UART") (pin "1") (pinfunction "1_1") (pintype "passive"))
    )
    (net (code "213") (name "UART_TXD") (class "Default")
      (node (ref "SOCKET_2") (pin "3") (pinfunction "3_3") (pintype "passive"))
      (node (ref "UART") (pin "3") (pinfunction "3_3") (pintype "passive"))
    )
    (net (code "214") (name "USBCLK") (class "Default")
      (node (ref "SOCKET_8") (pin "26") (pinfunction "26_26") (pintype "passive"))
    )
    (net (code "215") (name "USBFULLSPEED") (class "Default")
      (node (ref "SOCKET_1") (pin "6") (pinfunction "6_6") (pintype "passive"))
    )
    (net (code "216") (name "USBWIRECTRLOUT") (class "Default")
      (node (ref "SOCKET_1") (pin "4") (pinfunction "4_4") (pintype "passive"))
    )
    (net (code "217") (name "USBWIREDATAIN[0]") (class "Default")
      (node (ref "SOCKET_8") (pin "30") (pinfunction "30_30") (pintype "passive"))
    )
    (net (code "218") (name "USBWIREDATAIN[1]") (class "Default")
      (node (ref "SOCKET_8") (pin "28") (pinfunction "28_28") (pintype "passive"))
    )
    (net (code "219") (name "USBWIREDATAOUT[0]") (class "Default")
      (node (ref "SOCKET_1") (pin "2") (pinfunction "2_2") (pintype "passive"))
    )
    (net (code "220") (name "USBWIREDATAOUT[1]") (class "Default")
      (node (ref "SOCKET_8") (pin "32") (pinfunction "32_32") (pintype "passive"))
    )
    (net (code "221") (name "VDDO") (class "Default")
      (node (ref "C1") (pin "1") (pinfunction "1_1") (pintype "passive"))
      (node (ref "C3") (pin "1") (pinfunction "1_1") (pintype "passive"))
      (node (ref "IC1") (pin "10") (pinfunction "OE_10") (pintype "bidirectional"))
      (node (ref "IC1") (pin "2") (pinfunction "VCCA_2") (pintype "bidirectional"))
      (node (ref "IC2") (pin "10") (pinfunction "OE_10") (pintype "bidirectional"))
      (node (ref "IC2") (pin "2") (pinfunction "VCCA_2") (pintype "bidirectional"))
      (node (ref "POWER") (pin "6") (pinfunction "6_6") (pintype "passive"))
      (node (ref "POWER_LED") (pin "5") (pinfunction "5_5") (pintype "passive"))
    )
    (net (code "222") (name "VDDO_LED") (class "Default")
      (node (ref "POWER_LED") (pin "6") (pinfunction "6_6") (pintype "passive"))
      (node (ref "Q1") (pin "1") (pinfunction "G_1") (pintype "bidirectional"))
      (node (ref "R12") (pin "2") (pinfunction "2_2") (pintype "passive"))
    )
    (net (code "223") (name "VDD_1.8_1") (class "Default")
      (node (ref "C10") (pin "1") (pinfunction "1_1") (pintype "passive"))
      (node (ref "IC5") (pin "2") (pinfunction "VOUT_1_2") (pintype "bidirectional"))
      (node (ref "IC5") (pin "4") (pinfunction "VOUT_2_4") (pintype "bidirectional"))
      (node (ref "POWER") (pin "5") (pinfunction "5_5") (pintype "passive"))
    )
    (net (code "224") (name "VDD_1.8_2") (class "Default")
      (node (ref "C6") (pin "1") (pinfunction "1_1") (pintype "passive"))
      (node (ref "IC3") (pin "2") (pinfunction "VOUT_1_2") (pintype "bidirectional"))
      (node (ref "IC3") (pin "4") (pinfunction "VOUT_2_4") (pintype "bidirectional"))
      (node (ref "POWER") (pin "3") (pinfunction "3_3") (pintype "passive"))
    )
    (net (code "225") (name "VDD_1.8_3") (class "Default")
      (node (ref "C8") (pin "1") (pinfunction "1_1") (pintype "passive"))
      (node (ref "IC4") (pin "2") (pinfunction "VOUT_1_2") (pintype "bidirectional"))
      (node (ref "IC4") (pin "4") (pinfunction "VOUT_2_4") (pintype "bidirectional"))
      (node (ref "POWER") (pin "1") (pinfunction "1_1") (pintype "passive"))
    )
    (net (code "226") (name "VDD_3V3") (class "Default")
      (node (ref "3.3V_GPIO") (pin "1") (pinfunction "1_1") (pintype "passive"))
      (node (ref "C2") (pin "1") (pinfunction "1_1") (pintype "passive"))
      (node (ref "C4") (pin "1") (pinfunction "1_1") (pintype "passive"))
      (node (ref "C5") (pin "1") (pinfunction "1_1") (pintype "passive"))
      (node (ref "C7") (pin "1") (pinfunction "1_1") (pintype "passive"))
      (node (ref "C9") (pin "1") (pinfunction "1_1") (pintype "passive"))
      (node (ref "FLASH") (pin "1") (pinfunction "1_1") (pintype "passive"))
      (node (ref "FLASH") (pin "2") (pinfunction "2_2") (pintype "passive"))
      (node (ref "IC1") (pin "19") (pinfunction "VCCB_19") (pintype "bidirectional"))
      (node (ref "IC2") (pin "19") (pinfunction "VCCB_19") (pintype "bidirectional"))
      (node (ref "IC3") (pin "3") (pinfunction "VIN_3") (pintype "bidirectional"))
      (node (ref "IC4") (pin "3") (pinfunction "VIN_3") (pintype "bidirectional"))
      (node (ref "IC5") (pin "3") (pinfunction "VIN_3") (pintype "bidirectional"))
      (node (ref "JTAG_20_PIN") (pin "1") (pinfunction "1_1") (pintype "passive"))
      (node (ref "JTAG_20_PIN") (pin "2") (pinfunction "2_2") (pintype "passive"))
      (node (ref "Q3") (pin "1") (pinfunction "G_1") (pintype "bidirectional"))
      (node (ref "R11") (pin "2") (pinfunction "2_2") (pintype "passive"))
      (node (ref "R13") (pin "2") (pinfunction "2_2") (pintype "passive"))
      (node (ref "R15") (pin "2") (pinfunction "2_2") (pintype "passive"))
      (node (ref "R16") (pin "2") (pinfunction "2_2") (pintype "passive"))
      (node (ref "R17") (pin "2") (pinfunction "2_2") (pintype "passive"))
      (node (ref "SD_CARD") (pin "1") (pinfunction "1_1") (pintype "passive"))
      (node (ref "SD_CARD") (pin "2") (pinfunction "2_2") (pintype "passive"))
      (node (ref "USB-UART_1") (pin "3") (pinfunction "3_3") (pintype "passive"))
    )
    (net (code "227") (name "VDD_3V3_GPIO") (class "Default")
      (node (ref "3.3V_GPIO") (pin "2") (pinfunction "2_2") (pintype "passive"))
      (node (ref "GPIO0") (pin "29") (pinfunction "29_29") (pintype "passive"))
      (node (ref "GPIO1") (pin "29") (pinfunction "29_29") (pintype "passive"))
      (node (ref "GPIO2") (pin "29") (pinfunction "29_29") (pintype "passive"))
      (node (ref "GPIO3") (pin "29") (pinfunction "29_29") (pintype "passive"))
    )
    (net (code "228") (name "VDD_5V_USB") (class "Default")
      (node (ref "USB-UART_2") (pin "2") (pinfunction "2_2") (pintype "passive"))
    )
    (net (code "229") (name "VDD_CHIP") (class "Default")
      (node (ref "C12") (pin "1") (pinfunction "1_1") (pintype "passive"))
      (node (ref "C13") (pin "1") (pinfunction "1_1") (pintype "passive"))
      (node (ref "POWER") (pin "2") (pinfunction "2_2") (pintype "passive"))
      (node (ref "POWER_LED") (pin "1") (pinfunction "1_1") (pintype "passive"))
      (node (ref "SOCKET_1") (pin "16") (pinfunction "16_16") (pintype "passive"))
      (node (ref "SOCKET_2") (pin "16") (pinfunction "16_16") (pintype "passive"))
      (node (ref "SOCKET_3") (pin "16") (pinfunction "16_16") (pintype "passive"))
      (node (ref "SOCKET_4") (pin "16") (pinfunction "16_16") (pintype "passive"))
      (node (ref "SOCKET_5") (pin "16") (pinfunction "16_16") (pintype "passive"))
      (node (ref "SOCKET_6") (pin "16") (pinfunction "16_16") (pintype "passive"))
      (node (ref "SOCKET_7") (pin "16") (pinfunction "16_16") (pintype "passive"))
      (node (ref "SOCKET_8") (pin "16") (pinfunction "16_16") (pintype "passive"))
    )
    (net (code "230") (name "VDD_CHIP_IO") (class "Default")
      (node (ref "C11") (pin "1") (pinfunction "1_1") (pintype "passive"))
      (node (ref "C14") (pin "1") (pinfunction "1_1") (pintype "passive"))
      (node (ref "POWER") (pin "4") (pinfunction "4_4") (pintype "passive"))
      (node (ref "POWER_LED") (pin "3") (pinfunction "3_3") (pintype "passive"))
      (node (ref "SOCKET_1") (pin "24") (pinfunction "24_24") (pintype "passive"))
      (node (ref "SOCKET_2") (pin "19") (pinfunction "19_19") (pintype "passive"))
      (node (ref "SOCKET_3") (pin "24") (pinfunction "24_24") (pintype "passive"))
      (node (ref "SOCKET_4") (pin "19") (pinfunction "19_19") (pintype "passive"))
      (node (ref "SOCKET_5") (pin "24") (pinfunction "24_24") (pintype "passive"))
      (node (ref "SOCKET_6") (pin "19") (pinfunction "19_19") (pintype "passive"))
      (node (ref "SOCKET_7") (pin "24") (pinfunction "24_24") (pintype "passive"))
      (node (ref "SOCKET_8") (pin "19") (pinfunction "19_19") (pintype "passive"))
    )
    (net (code "231") (name "VDD_CHIP_IO_LED") (class "Default")
      (node (ref "POWER_LED") (pin "4") (pinfunction "4_4") (pintype "passive"))
      (node (ref "Q2") (pin "1") (pinfunction "G_1") (pintype "bidirectional"))
      (node (ref "R14") (pin "2") (pinfunction "2_2") (pintype "passive"))
    )
    (net (code "232") (name "VDD_CHIP_LED") (class "Default")
      (node (ref "POWER_LED") (pin "2") (pinfunction "2_2") (pintype "passive"))
      (node (ref "Q4") (pin "1") (pinfunction "G_1") (pintype "bidirectional"))
      (node (ref "R10") (pin "2") (pinfunction "2_2") (pintype "passive"))
    )
    (net (code "233") (name "unconnected-(FLASH-Pad5)") (class "Default")
      (node (ref "FLASH") (pin "5") (pinfunction "5_5") (pintype "passive"))
    )
    (net (code "234") (name "unconnected-(FLASH-Pad7)") (class "Default")
      (node (ref "FLASH") (pin "7") (pinfunction "7_7") (pintype "passive"))
    )
    (net (code "235") (name "unconnected-(FLASH-Pad9)") (class "Default")
      (node (ref "FLASH") (pin "9") (pinfunction "9_9") (pintype "passive"))
    )
    (net (code "236") (name "unconnected-(FLASH-Pad11)") (class "Default")
      (node (ref "FLASH") (pin "11") (pinfunction "11_11") (pintype "passive"))
    )
    (net (code "237") (name "unconnected-(GPIO0-Pad11)") (class "Default")
      (node (ref "GPIO0") (pin "11") (pinfunction "11_11") (pintype "passive"))
    )
    (net (code "238") (name "unconnected-(GPIO1-Pad11)") (class "Default")
      (node (ref "GPIO1") (pin "11") (pinfunction "11_11") (pintype "passive"))
    )
    (net (code "239") (name "unconnected-(GPIO2-Pad1)") (class "Default")
      (node (ref "GPIO2") (pin "1") (pinfunction "1_1") (pintype "passive"))
    )
    (net (code "240") (name "unconnected-(GPIO2-Pad3)") (class "Default")
      (node (ref "GPIO2") (pin "3") (pinfunction "3_3") (pintype "passive"))
    )
    (net (code "241") (name "unconnected-(GPIO2-Pad11)") (class "Default")
      (node (ref "GPIO2") (pin "11") (pinfunction "11_11") (pintype "passive"))
    )
    (net (code "242") (name "unconnected-(GPIO3-Pad11)") (class "Default")
      (node (ref "GPIO3") (pin "11") (pinfunction "11_11") (pintype "passive"))
    )
    (net (code "243") (name "unconnected-(IC2-A1-Pad1)") (class "Default")
      (node (ref "IC2") (pin "1") (pinfunction "A1_1") (pintype "bidirectional"))
    )
    (net (code "244") (name "unconnected-(IC2-A2-Pad3)") (class "Default")
      (node (ref "IC2") (pin "3") (pinfunction "A2_3") (pintype "bidirectional"))
    )
    (net (code "245") (name "unconnected-(IC2-B1-Pad20)") (class "Default")
      (node (ref "IC2") (pin "20") (pinfunction "B1_20") (pintype "bidirectional"))
    )
    (net (code "246") (name "unconnected-(IC2-B2-Pad18)") (class "Default")
      (node (ref "IC2") (pin "18") (pinfunction "B2_18") (pintype "bidirectional"))
    )
    (net (code "247") (name "unconnected-(JTAG_20_PIN-Pad3)") (class "Default")
      (node (ref "JTAG_20_PIN") (pin "3") (pinfunction "3_3") (pintype "passive"))
    )
    (net (code "248") (name "unconnected-(JTAG_20_PIN-Pad11)") (class "Default")
      (node (ref "JTAG_20_PIN") (pin "11") (pinfunction "11_11") (pintype "passive"))
    )
    (net (code "249") (name "unconnected-(JTAG_20_PIN-Pad15)") (class "Default")
      (node (ref "JTAG_20_PIN") (pin "15") (pinfunction "15_15") (pintype "passive"))
    )
    (net (code "250") (name "unconnected-(JTAG_20_PIN-Pad17)") (class "Default")
      (node (ref "JTAG_20_PIN") (pin "17") (pinfunction "17_17") (pintype "passive"))
    )
    (net (code "251") (name "unconnected-(JTAG_20_PIN-Pad19)") (class "Default")
      (node (ref "JTAG_20_PIN") (pin "19") (pinfunction "19_19") (pintype "passive"))
    )
    (net (code "252") (name "unconnected-(SD_CARD-Pad5)") (class "Default")
      (node (ref "SD_CARD") (pin "5") (pinfunction "5_5") (pintype "passive"))
    )
    (net (code "253") (name "unconnected-(SD_CARD-Pad7)") (class "Default")
      (node (ref "SD_CARD") (pin "7") (pinfunction "7_7") (pintype "passive"))
    )
    (net (code "254") (name "unconnected-(SD_CARD-Pad9)") (class "Default")
      (node (ref "SD_CARD") (pin "9") (pinfunction "9_9") (pintype "passive"))
    )
    (net (code "255") (name "unconnected-(SD_CARD-Pad11)") (class "Default")
      (node (ref "SD_CARD") (pin "11") (pinfunction "11_11") (pintype "passive"))
    )
    (net (code "256") (name "unconnected-(SOCKET_1-Pad1)") (class "Default")
      (node (ref "SOCKET_1") (pin "1") (pinfunction "1_1") (pintype "passive"))
    )
    (net (code "257") (name "unconnected-(SOCKET_1-Pad3)") (class "Default")
      (node (ref "SOCKET_1") (pin "3") (pinfunction "3_3") (pintype "passive"))
    )
    (net (code "258") (name "unconnected-(SOCKET_1-Pad5)") (class "Default")
      (node (ref "SOCKET_1") (pin "5") (pinfunction "5_5") (pintype "passive"))
    )
    (net (code "259") (name "unconnected-(SOCKET_2-Pad12)") (class "Default")
      (node (ref "SOCKET_2") (pin "12") (pinfunction "12_12") (pintype "passive"))
    )
    (net (code "260") (name "unconnected-(SOCKET_2-Pad13)") (class "Default")
      (node (ref "SOCKET_2") (pin "13") (pinfunction "13_13") (pintype "passive"))
    )
    (net (code "261") (name "unconnected-(SOCKET_2-Pad29)") (class "Default")
      (node (ref "SOCKET_2") (pin "29") (pinfunction "29_29") (pintype "passive"))
    )
    (net (code "262") (name "unconnected-(SOCKET_2-Pad30)") (class "Default")
      (node (ref "SOCKET_2") (pin "30") (pinfunction "30_30") (pintype "passive"))
    )
    (net (code "263") (name "unconnected-(SOCKET_2-Pad31)") (class "Default")
      (node (ref "SOCKET_2") (pin "31") (pinfunction "31_31") (pintype "passive"))
    )
    (net (code "264") (name "unconnected-(SOCKET_2-Pad32)") (class "Default")
      (node (ref "SOCKET_2") (pin "32") (pinfunction "32_32") (pintype "passive"))
    )
    (net (code "265") (name "unconnected-(SOCKET_3-Pad1)") (class "Default")
      (node (ref "SOCKET_3") (pin "1") (pinfunction "1_1") (pintype "passive"))
    )
    (net (code "266") (name "unconnected-(SOCKET_3-Pad2)") (class "Default")
      (node (ref "SOCKET_3") (pin "2") (pinfunction "2_2") (pintype "passive"))
    )
    (net (code "267") (name "unconnected-(SOCKET_3-Pad3)") (class "Default")
      (node (ref "SOCKET_3") (pin "3") (pinfunction "3_3") (pintype "passive"))
    )
    (net (code "268") (name "unconnected-(SOCKET_3-Pad4)") (class "Default")
      (node (ref "SOCKET_3") (pin "4") (pinfunction "4_4") (pintype "passive"))
    )
    (net (code "269") (name "unconnected-(SOCKET_3-Pad5)") (class "Default")
      (node (ref "SOCKET_3") (pin "5") (pinfunction "5_5") (pintype "passive"))
    )
    (net (code "270") (name "unconnected-(SOCKET_3-Pad6)") (class "Default")
      (node (ref "SOCKET_3") (pin "6") (pinfunction "6_6") (pintype "passive"))
    )
    (net (code "271") (name "unconnected-(SOCKET_4-Pad26)") (class "Default")
      (node (ref "SOCKET_4") (pin "26") (pinfunction "26_26") (pintype "passive"))
    )
    (net (code "272") (name "unconnected-(SOCKET_4-Pad27)") (class "Default")
      (node (ref "SOCKET_4") (pin "27") (pinfunction "27_27") (pintype "passive"))
    )
    (net (code "273") (name "unconnected-(SOCKET_4-Pad28)") (class "Default")
      (node (ref "SOCKET_4") (pin "28") (pinfunction "28_28") (pintype "passive"))
    )
    (net (code "274") (name "unconnected-(SOCKET_4-Pad29)") (class "Default")
      (node (ref "SOCKET_4") (pin "29") (pinfunction "29_29") (pintype "passive"))
    )
    (net (code "275") (name "unconnected-(SOCKET_4-Pad30)") (class "Default")
      (node (ref "SOCKET_4") (pin "30") (pinfunction "30_30") (pintype "passive"))
    )
    (net (code "276") (name "unconnected-(SOCKET_4-Pad31)") (class "Default")
      (node (ref "SOCKET_4") (pin "31") (pinfunction "31_31") (pintype "passive"))
    )
    (net (code "277") (name "unconnected-(SOCKET_4-Pad32)") (class "Default")
      (node (ref "SOCKET_4") (pin "32") (pinfunction "32_32") (pintype "passive"))
    )
    (net (code "278") (name "unconnected-(SOCKET_5-Pad1)") (class "Default")
      (node (ref "SOCKET_5") (pin "1") (pinfunction "1_1") (pintype "passive"))
    )
    (net (code "279") (name "unconnected-(SOCKET_5-Pad2)") (class "Default")
      (node (ref "SOCKET_5") (pin "2") (pinfunction "2_2") (pintype "passive"))
    )
    (net (code "280") (name "unconnected-(SOCKET_5-Pad3)") (class "Default")
      (node (ref "SOCKET_5") (pin "3") (pinfunction "3_3") (pintype "passive"))
    )
    (net (code "281") (name "unconnected-(SOCKET_5-Pad4)") (class "Default")
      (node (ref "SOCKET_5") (pin "4") (pinfunction "4_4") (pintype "passive"))
    )
    (net (code "282") (name "unconnected-(SOCKET_5-Pad5)") (class "Default")
      (node (ref "SOCKET_5") (pin "5") (pinfunction "5_5") (pintype "passive"))
    )
    (net (code "283") (name "unconnected-(SOCKET_5-Pad6)") (class "Default")
      (node (ref "SOCKET_5") (pin "6") (pinfunction "6_6") (pintype "passive"))
    )
    (net (code "284") (name "unconnected-(SOCKET_6-Pad26)") (class "Default")
      (node (ref "SOCKET_6") (pin "26") (pinfunction "26_26") (pintype "passive"))
    )
    (net (code "285") (name "unconnected-(SOCKET_6-Pad27)") (class "Default")
      (node (ref "SOCKET_6") (pin "27") (pinfunction "27_27") (pintype "passive"))
    )
    (net (code "286") (name "unconnected-(SOCKET_6-Pad28)") (class "Default")
      (node (ref "SOCKET_6") (pin "28") (pinfunction "28_28") (pintype "passive"))
    )
    (net (code "287") (name "unconnected-(SOCKET_6-Pad29)") (class "Default")
      (node (ref "SOCKET_6") (pin "29") (pinfunction "29_29") (pintype "passive"))
    )
    (net (code "288") (name "unconnected-(SOCKET_6-Pad30)") (class "Default")
      (node (ref "SOCKET_6") (pin "30") (pinfunction "30_30") (pintype "passive"))
    )
    (net (code "289") (name "unconnected-(SOCKET_6-Pad31)") (class "Default")
      (node (ref "SOCKET_6") (pin "31") (pinfunction "31_31") (pintype "passive"))
    )
    (net (code "290") (name "unconnected-(SOCKET_6-Pad32)") (class "Default")
      (node (ref "SOCKET_6") (pin "32") (pinfunction "32_32") (pintype "passive"))
    )
    (net (code "291") (name "unconnected-(SOCKET_7-Pad1)") (class "Default")
      (node (ref "SOCKET_7") (pin "1") (pinfunction "1_1") (pintype "passive"))
    )
    (net (code "292") (name "unconnected-(SOCKET_7-Pad2)") (class "Default")
      (node (ref "SOCKET_7") (pin "2") (pinfunction "2_2") (pintype "passive"))
    )
    (net (code "293") (name "unconnected-(SOCKET_7-Pad3)") (class "Default")
      (node (ref "SOCKET_7") (pin "3") (pinfunction "3_3") (pintype "passive"))
    )
    (net (code "294") (name "unconnected-(SOCKET_7-Pad4)") (class "Default")
      (node (ref "SOCKET_7") (pin "4") (pinfunction "4_4") (pintype "passive"))
    )
    (net (code "295") (name "unconnected-(SOCKET_7-Pad5)") (class "Default")
      (node (ref "SOCKET_7") (pin "5") (pinfunction "5_5") (pintype "passive"))
    )
    (net (code "296") (name "unconnected-(SOCKET_7-Pad6)") (class "Default")
      (node (ref "SOCKET_7") (pin "6") (pinfunction "6_6") (pintype "passive"))
    )
    (net (code "297") (name "unconnected-(SOCKET_8-Pad27)") (class "Default")
      (node (ref "SOCKET_8") (pin "27") (pinfunction "27_27") (pintype "passive"))
    )
    (net (code "298") (name "unconnected-(SOCKET_8-Pad29)") (class "Default")
      (node (ref "SOCKET_8") (pin "29") (pinfunction "29_29") (pintype "passive"))
    )
    (net (code "299") (name "unconnected-(SOCKET_8-Pad31)") (class "Default")
      (node (ref "SOCKET_8") (pin "31") (pinfunction "31_31") (pintype "passive"))
    )
    (net (code "300") (name "unconnected-(USB-UART_2-Pad1)") (class "Default")
      (node (ref "USB-UART_2") (pin "1") (pinfunction "1_1") (pintype "passive"))
    )
    (net (code "301") (name "unconnected-(USB-UART_2-Pad3)") (class "Default")
      (node (ref "USB-UART_2") (pin "3") (pinfunction "3_3") (pintype "passive"))
    )
    (net (code "302") (name "unconnected-(USB-UART_2-Pad4)") (class "Default")
      (node (ref "USB-UART_2") (pin "4") (pinfunction "4_4") (pintype "passive"))
    )
  )
)
